# Lyra_Main_4_Panel.net
KiCad netlist of a schematic drawn in EAGLE
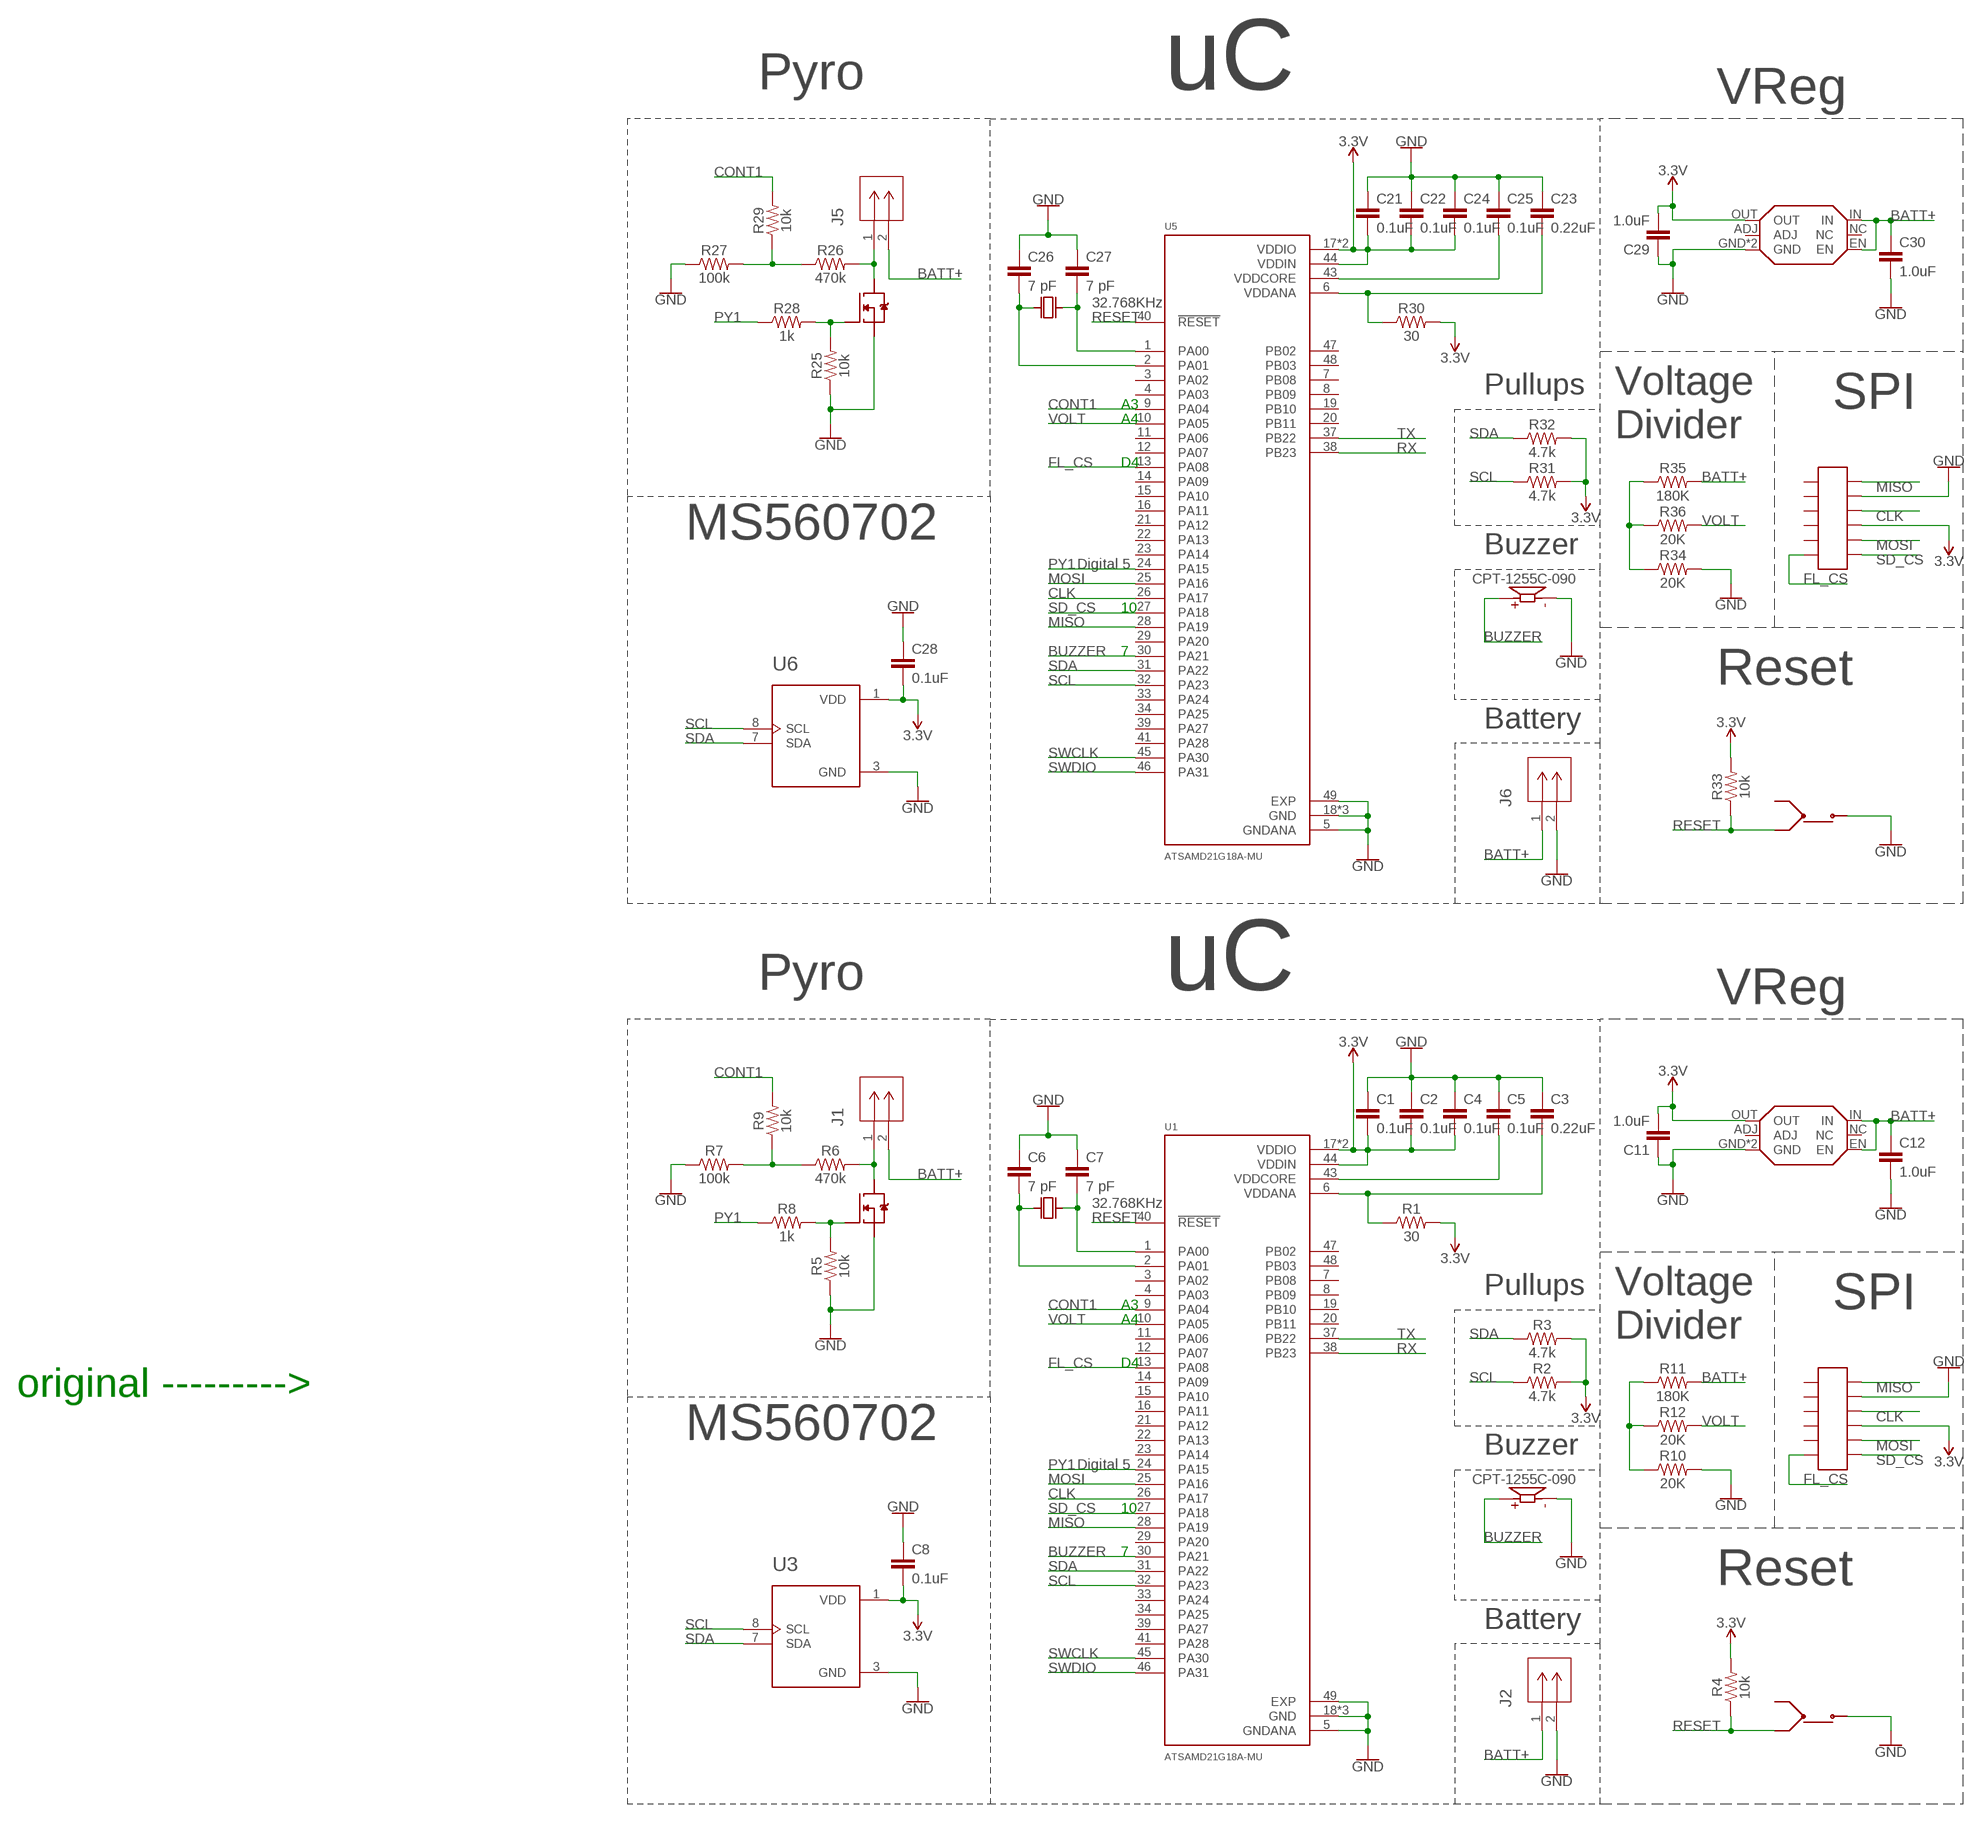
[diagram p0: schematic, sheet 1, part 1 of 2]
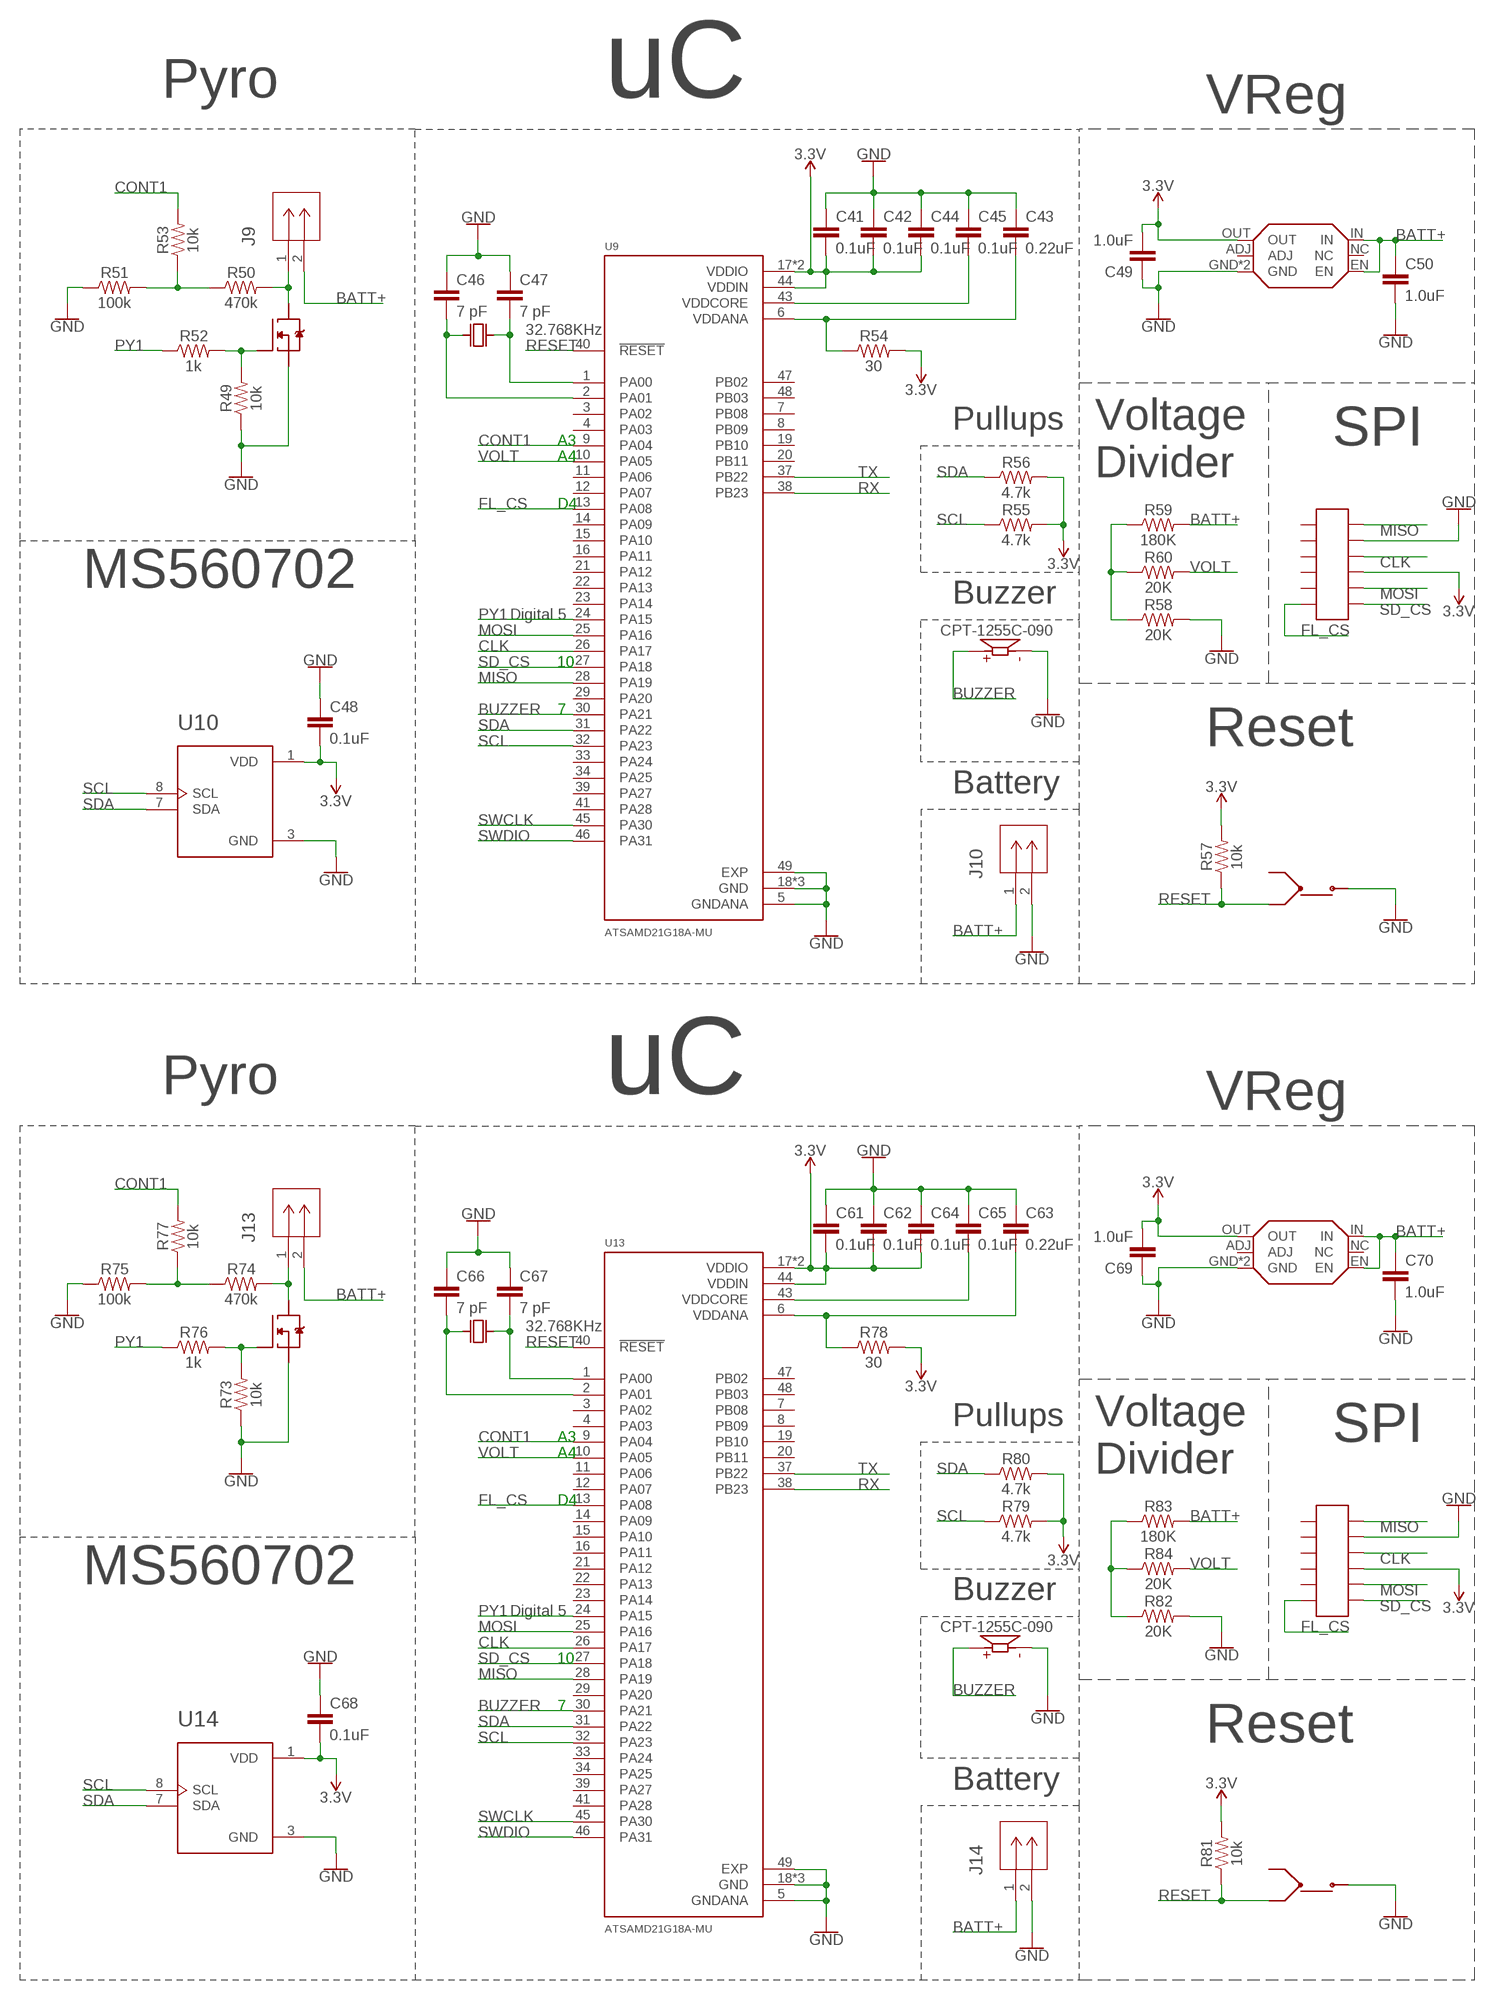
[diagram p1: schematic, sheet 1, part 2 of 2]

(export (version "E")
  (design (tool "Eeschema 10.0.6"))
  (components
    (comp (ref "C1")
      (value "0.1uF")
      (footprint "eagle-import:0603")
      (libsource (lib "eagle-import") (part "0.1UF-0603-25V-(+80/-20%)"))
    )
    (comp (ref "C2")
      (value "0.1uF")
      (footprint "eagle-import:0603")
      (libsource (lib "eagle-import") (part "0.1UF-0603-25V-(+80/-20%)"))
    )
    (comp (ref "C3")
      (value "0.22uF")
      (footprint "eagle-import:0603")
      (libsource (lib "eagle-import") (part "0.1UF-0603-25V-(+80/-20%)"))
    )
    (comp (ref "C4")
      (value "0.1uF")
      (footprint "eagle-import:0603")
      (libsource (lib "eagle-import") (part "0.1UF-0603-25V-(+80/-20%)"))
    )
    (comp (ref "C5")
      (value "0.1uF")
      (footprint "eagle-import:0603")
      (libsource (lib "eagle-import") (part "0.1UF-0603-25V-(+80/-20%)"))
    )
    (comp (ref "C6")
      (value "7 pF")
      (footprint "eagle-import:0402")
      (libsource (lib "eagle-import") (part "0.1UF-0402-16V-10%"))
    )
    (comp (ref "C7")
      (value "7 pF")
      (footprint "eagle-import:0402")
      (libsource (lib "eagle-import") (part "0.1UF-0402-16V-10%"))
    )
    (comp (ref "C8")
      (value "0.1uF")
      (footprint "eagle-import:0603")
      (libsource (lib "eagle-import") (part "0.1UF-0603-25V-(+80/-20%)"))
    )
    (comp (ref "C11")
      (value "1.0uF")
      (footprint "eagle-import:0402")
      (libsource (lib "eagle-import") (part "1.0UF-0402-16V-10%"))
    )
    (comp (ref "C12")
      (value "1.0uF")
      (footprint "eagle-import:0402")
      (libsource (lib "eagle-import") (part "1.0UF-0402-16V-10%"))
    )
    (comp (ref "C21")
      (value "0.1uF")
      (footprint "eagle-import:0603")
      (libsource (lib "eagle-import") (part "0.1UF-0603-25V-(+80/-20%)"))
    )
    (comp (ref "C22")
      (value "0.1uF")
      (footprint "eagle-import:0603")
      (libsource (lib "eagle-import") (part "0.1UF-0603-25V-(+80/-20%)"))
    )
    (comp (ref "C23")
      (value "0.22uF")
      (footprint "eagle-import:0603")
      (libsource (lib "eagle-import") (part "0.1UF-0603-25V-(+80/-20%)"))
    )
    (comp (ref "C24")
      (value "0.1uF")
      (footprint "eagle-import:0603")
      (libsource (lib "eagle-import") (part "0.1UF-0603-25V-(+80/-20%)"))
    )
    (comp (ref "C25")
      (value "0.1uF")
      (footprint "eagle-import:0603")
      (libsource (lib "eagle-import") (part "0.1UF-0603-25V-(+80/-20%)"))
    )
    (comp (ref "C26")
      (value "7 pF")
      (footprint "eagle-import:0402")
      (libsource (lib "eagle-import") (part "0.1UF-0402-16V-10%"))
    )
    (comp (ref "C27")
      (value "7 pF")
      (footprint "eagle-import:0402")
      (libsource (lib "eagle-import") (part "0.1UF-0402-16V-10%"))
    )
    (comp (ref "C28")
      (value "0.1uF")
      (footprint "eagle-import:0603")
      (libsource (lib "eagle-import") (part "0.1UF-0603-25V-(+80/-20%)"))
    )
    (comp (ref "C29")
      (value "1.0uF")
      (footprint "eagle-import:0402")
      (libsource (lib "eagle-import") (part "1.0UF-0402-16V-10%"))
    )
    (comp (ref "C30")
      (value "1.0uF")
      (footprint "eagle-import:0402")
      (libsource (lib "eagle-import") (part "1.0UF-0402-16V-10%"))
    )
    (comp (ref "C41")
      (value "0.1uF")
      (footprint "eagle-import:0603")
      (libsource (lib "eagle-import") (part "0.1UF-0603-25V-(+80/-20%)"))
    )
    (comp (ref "C42")
      (value "0.1uF")
      (footprint "eagle-import:0603")
      (libsource (lib "eagle-import") (part "0.1UF-0603-25V-(+80/-20%)"))
    )
    (comp (ref "C43")
      (value "0.22uF")
      (footprint "eagle-import:0603")
      (libsource (lib "eagle-import") (part "0.1UF-0603-25V-(+80/-20%)"))
    )
    (comp (ref "C44")
      (value "0.1uF")
      (footprint "eagle-import:0603")
      (libsource (lib "eagle-import") (part "0.1UF-0603-25V-(+80/-20%)"))
    )
    (comp (ref "C45")
      (value "0.1uF")
      (footprint "eagle-import:0603")
      (libsource (lib "eagle-import") (part "0.1UF-0603-25V-(+80/-20%)"))
    )
    (comp (ref "C46")
      (value "7 pF")
      (footprint "eagle-import:0402")
      (libsource (lib "eagle-import") (part "0.1UF-0402-16V-10%"))
    )
    (comp (ref "C47")
      (value "7 pF")
      (footprint "eagle-import:0402")
      (libsource (lib "eagle-import") (part "0.1UF-0402-16V-10%"))
    )
    (comp (ref "C48")
      (value "0.1uF")
      (footprint "eagle-import:0603")
      (libsource (lib "eagle-import") (part "0.1UF-0603-25V-(+80/-20%)"))
    )
    (comp (ref "C49")
      (value "1.0uF")
      (footprint "eagle-import:0402")
      (libsource (lib "eagle-import") (part "1.0UF-0402-16V-10%"))
    )
    (comp (ref "C50")
      (value "1.0uF")
      (footprint "eagle-import:0402")
      (libsource (lib "eagle-import") (part "1.0UF-0402-16V-10%"))
    )
    (comp (ref "C61")
      (value "0.1uF")
      (footprint "eagle-import:0603")
      (libsource (lib "eagle-import") (part "0.1UF-0603-25V-(+80/-20%)"))
    )
    (comp (ref "C62")
      (value "0.1uF")
      (footprint "eagle-import:0603")
      (libsource (lib "eagle-import") (part "0.1UF-0603-25V-(+80/-20%)"))
    )
    (comp (ref "C63")
      (value "0.22uF")
      (footprint "eagle-import:0603")
      (libsource (lib "eagle-import") (part "0.1UF-0603-25V-(+80/-20%)"))
    )
    (comp (ref "C64")
      (value "0.1uF")
      (footprint "eagle-import:0603")
      (libsource (lib "eagle-import") (part "0.1UF-0603-25V-(+80/-20%)"))
    )
    (comp (ref "C65")
      (value "0.1uF")
      (footprint "eagle-import:0603")
      (libsource (lib "eagle-import") (part "0.1UF-0603-25V-(+80/-20%)"))
    )
    (comp (ref "C66")
      (value "7 pF")
      (footprint "eagle-import:0402")
      (libsource (lib "eagle-import") (part "0.1UF-0402-16V-10%"))
    )
    (comp (ref "C67")
      (value "7 pF")
      (footprint "eagle-import:0402")
      (libsource (lib "eagle-import") (part "0.1UF-0402-16V-10%"))
    )
    (comp (ref "C68")
      (value "0.1uF")
      (footprint "eagle-import:0603")
      (libsource (lib "eagle-import") (part "0.1UF-0603-25V-(+80/-20%)"))
    )
    (comp (ref "C69")
      (value "1.0uF")
      (footprint "eagle-import:0402")
      (libsource (lib "eagle-import") (part "1.0UF-0402-16V-10%"))
    )
    (comp (ref "C70")
      (value "1.0uF")
      (footprint "eagle-import:0402")
      (libsource (lib "eagle-import") (part "1.0UF-0402-16V-10%"))
    )
    (comp (ref "J1")
      (value "OSTVN02A150")
      (footprint "eagle-import:CONN_OSTVN02A150_OST")
      (fields (field (name "COPYRIGHT") "Copyright (C) 2018 Accelerated Designs. All rights reserved"))
      (libsource (lib "eagle-import") (part "OSTVN02A150"))
    )
    (comp (ref "J2")
      (value "OSTVN02A150")
      (footprint "eagle-import:CONN_OSTVN02A150_OST")
      (fields (field (name "COPYRIGHT") "Copyright (C) 2018 Accelerated Designs. All rights reserved"))
      (libsource (lib "eagle-import") (part "OSTVN02A150"))
    )
    (comp (ref "J5")
      (value "OSTVN02A150")
      (footprint "eagle-import:CONN_OSTVN02A150_OST")
      (fields (field (name "COPYRIGHT") "Copyright (C) 2018 Accelerated Designs. All rights reserved"))
      (libsource (lib "eagle-import") (part "OSTVN02A150"))
    )
    (comp (ref "J6")
      (value "OSTVN02A150")
      (footprint "eagle-import:CONN_OSTVN02A150_OST")
      (fields (field (name "COPYRIGHT") "Copyright (C) 2018 Accelerated Designs. All rights reserved"))
      (libsource (lib "eagle-import") (part "OSTVN02A150"))
    )
    (comp (ref "J9")
      (value "OSTVN02A150")
      (footprint "eagle-import:CONN_OSTVN02A150_OST")
      (fields (field (name "COPYRIGHT") "Copyright (C) 2018 Accelerated Designs. All rights reserved"))
      (libsource (lib "eagle-import") (part "OSTVN02A150"))
    )
    (comp (ref "J10")
      (value "OSTVN02A150")
      (footprint "eagle-import:CONN_OSTVN02A150_OST")
      (fields (field (name "COPYRIGHT") "Copyright (C) 2018 Accelerated Designs. All rights reserved"))
      (libsource (lib "eagle-import") (part "OSTVN02A150"))
    )
    (comp (ref "J13")
      (value "OSTVN02A150")
      (footprint "eagle-import:CONN_OSTVN02A150_OST")
      (fields (field (name "COPYRIGHT") "Copyright (C) 2018 Accelerated Designs. All rights reserved"))
      (libsource (lib "eagle-import") (part "OSTVN02A150"))
    )
    (comp (ref "J14")
      (value "OSTVN02A150")
      (footprint "eagle-import:CONN_OSTVN02A150_OST")
      (fields (field (name "COPYRIGHT") "Copyright (C) 2018 Accelerated Designs. All rights reserved"))
      (libsource (lib "eagle-import") (part "OSTVN02A150"))
    )
    (comp (ref "LS2")
      (value "CPT-1255C-090")
      (footprint "eagle-import:CUI_CPT-1255C-090")
      (fields (field (name "MF") "CUI Devices"))
      (libsource (lib "eagle-import") (part "CPT-1255C-090"))
    )
    (comp (ref "LS3")
      (value "CPT-1255C-090")
      (footprint "eagle-import:CUI_CPT-1255C-090")
      (fields (field (name "MF") "CUI Devices"))
      (libsource (lib "eagle-import") (part "CPT-1255C-090"))
    )
    (comp (ref "LS5")
      (value "CPT-1255C-090")
      (footprint "eagle-import:CUI_CPT-1255C-090")
      (fields (field (name "MF") "CUI Devices"))
      (libsource (lib "eagle-import") (part "CPT-1255C-090"))
    )
    (comp (ref "LS7")
      (value "CPT-1255C-090")
      (footprint "eagle-import:CUI_CPT-1255C-090")
      (fields (field (name "MF") "CUI Devices"))
      (libsource (lib "eagle-import") (part "CPT-1255C-090"))
    )
    (comp (ref "R1")
      (value "30")
      (footprint "eagle-import:0402")
      (libsource (lib "eagle-import") (part "RESISTOR0402"))
    )
    (comp (ref "R2")
      (value "4.7k")
      (footprint "eagle-import:0603")
      (libsource (lib "eagle-import") (part "4.7KOHM-0603-1/10W-1%"))
    )
    (comp (ref "R3")
      (value "4.7k")
      (footprint "eagle-import:0603")
      (libsource (lib "eagle-import") (part "4.7KOHM-0603-1/10W-1%"))
    )
    (comp (ref "R4")
      (value "10k")
      (footprint "eagle-import:0402")
      (libsource (lib "eagle-import") (part "RESISTOR0402"))
    )
    (comp (ref "R5")
      (value "10k")
      (footprint "eagle-import:0402")
      (libsource (lib "eagle-import") (part "RESISTOR0402"))
    )
    (comp (ref "R6")
      (value "470k")
      (footprint "eagle-import:0402")
      (libsource (lib "eagle-import") (part "RESISTOR0402"))
    )
    (comp (ref "R7")
      (value "100k")
      (footprint "eagle-import:0402")
      (libsource (lib "eagle-import") (part "RESISTOR0402"))
    )
    (comp (ref "R8")
      (value "1k")
      (footprint "eagle-import:0402")
      (libsource (lib "eagle-import") (part "RESISTOR0402"))
    )
    (comp (ref "R9")
      (value "10k")
      (footprint "eagle-import:0402")
      (libsource (lib "eagle-import") (part "RESISTOR0402"))
    )
    (comp (ref "R10")
      (value "20K")
      (footprint "eagle-import:0402")
      (libsource (lib "eagle-import") (part "RESISTOR0402"))
    )
    (comp (ref "R11")
      (value "180K")
      (footprint "eagle-import:0402")
      (libsource (lib "eagle-import") (part "RESISTOR0402"))
    )
    (comp (ref "R12")
      (value "20K")
      (footprint "eagle-import:0402")
      (libsource (lib "eagle-import") (part "RESISTOR0402"))
    )
    (comp (ref "R25")
      (value "10k")
      (footprint "eagle-import:0402")
      (libsource (lib "eagle-import") (part "RESISTOR0402"))
    )
    (comp (ref "R26")
      (value "470k")
      (footprint "eagle-import:0402")
      (libsource (lib "eagle-import") (part "RESISTOR0402"))
    )
    (comp (ref "R27")
      (value "100k")
      (footprint "eagle-import:0402")
      (libsource (lib "eagle-import") (part "RESISTOR0402"))
    )
    (comp (ref "R28")
      (value "1k")
      (footprint "eagle-import:0402")
      (libsource (lib "eagle-import") (part "RESISTOR0402"))
    )
    (comp (ref "R29")
      (value "10k")
      (footprint "eagle-import:0402")
      (libsource (lib "eagle-import") (part "RESISTOR0402"))
    )
    (comp (ref "R30")
      (value "30")
      (footprint "eagle-import:0402")
      (libsource (lib "eagle-import") (part "RESISTOR0402"))
    )
    (comp (ref "R31")
      (value "4.7k")
      (footprint "eagle-import:0603")
      (libsource (lib "eagle-import") (part "4.7KOHM-0603-1/10W-1%"))
    )
    (comp (ref "R32")
      (value "4.7k")
      (footprint "eagle-import:0603")
      (libsource (lib "eagle-import") (part "4.7KOHM-0603-1/10W-1%"))
    )
    (comp (ref "R33")
      (value "10k")
      (footprint "eagle-import:0402")
      (libsource (lib "eagle-import") (part "RESISTOR0402"))
    )
    (comp (ref "R34")
      (value "20K")
      (footprint "eagle-import:0402")
      (libsource (lib "eagle-import") (part "RESISTOR0402"))
    )
    (comp (ref "R35")
      (value "180K")
      (footprint "eagle-import:0402")
      (libsource (lib "eagle-import") (part "RESISTOR0402"))
    )
    (comp (ref "R36")
      (value "20K")
      (footprint "eagle-import:0402")
      (libsource (lib "eagle-import") (part "RESISTOR0402"))
    )
    (comp (ref "R49")
      (value "10k")
      (footprint "eagle-import:0402")
      (libsource (lib "eagle-import") (part "RESISTOR0402"))
    )
    (comp (ref "R50")
      (value "470k")
      (footprint "eagle-import:0402")
      (libsource (lib "eagle-import") (part "RESISTOR0402"))
    )
    (comp (ref "R51")
      (value "100k")
      (footprint "eagle-import:0402")
      (libsource (lib "eagle-import") (part "RESISTOR0402"))
    )
    (comp (ref "R52")
      (value "1k")
      (footprint "eagle-import:0402")
      (libsource (lib "eagle-import") (part "RESISTOR0402"))
    )
    (comp (ref "R53")
      (value "10k")
      (footprint "eagle-import:0402")
      (libsource (lib "eagle-import") (part "RESISTOR0402"))
    )
    (comp (ref "R54")
      (value "30")
      (footprint "eagle-import:0402")
      (libsource (lib "eagle-import") (part "RESISTOR0402"))
    )
    (comp (ref "R55")
      (value "4.7k")
      (footprint "eagle-import:0603")
      (libsource (lib "eagle-import") (part "4.7KOHM-0603-1/10W-1%"))
    )
    (comp (ref "R56")
      (value "4.7k")
      (footprint "eagle-import:0603")
      (libsource (lib "eagle-import") (part "4.7KOHM-0603-1/10W-1%"))
    )
    (comp (ref "R57")
      (value "10k")
      (footprint "eagle-import:0402")
      (libsource (lib "eagle-import") (part "RESISTOR0402"))
    )
    (comp (ref "R58")
      (value "20K")
      (footprint "eagle-import:0402")
      (libsource (lib "eagle-import") (part "RESISTOR0402"))
    )
    (comp (ref "R59")
      (value "180K")
      (footprint "eagle-import:0402")
      (libsource (lib "eagle-import") (part "RESISTOR0402"))
    )
    (comp (ref "R60")
      (value "20K")
      (footprint "eagle-import:0402")
      (libsource (lib "eagle-import") (part "RESISTOR0402"))
    )
    (comp (ref "R73")
      (value "10k")
      (footprint "eagle-import:0402")
      (libsource (lib "eagle-import") (part "RESISTOR0402"))
    )
    (comp (ref "R74")
      (value "470k")
      (footprint "eagle-import:0402")
      (libsource (lib "eagle-import") (part "RESISTOR0402"))
    )
    (comp (ref "R75")
      (value "100k")
      (footprint "eagle-import:0402")
      (libsource (lib "eagle-import") (part "RESISTOR0402"))
    )
    (comp (ref "R76")
      (value "1k")
      (footprint "eagle-import:0402")
      (libsource (lib "eagle-import") (part "RESISTOR0402"))
    )
    (comp (ref "R77")
      (value "10k")
      (footprint "eagle-import:0402")
      (libsource (lib "eagle-import") (part "RESISTOR0402"))
    )
    (comp (ref "R78")
      (value "30")
      (footprint "eagle-import:0402")
      (libsource (lib "eagle-import") (part "RESISTOR0402"))
    )
    (comp (ref "R79")
      (value "4.7k")
      (footprint "eagle-import:0603")
      (libsource (lib "eagle-import") (part "4.7KOHM-0603-1/10W-1%"))
    )
    (comp (ref "R80")
      (value "4.7k")
      (footprint "eagle-import:0603")
      (libsource (lib "eagle-import") (part "4.7KOHM-0603-1/10W-1%"))
    )
    (comp (ref "R81")
      (value "10k")
      (footprint "eagle-import:0402")
      (libsource (lib "eagle-import") (part "RESISTOR0402"))
    )
    (comp (ref "R82")
      (value "20K")
      (footprint "eagle-import:0402")
      (libsource (lib "eagle-import") (part "RESISTOR0402"))
    )
    (comp (ref "R83")
      (value "180K")
      (footprint "eagle-import:0402")
      (libsource (lib "eagle-import") (part "RESISTOR0402"))
    )
    (comp (ref "R84")
      (value "20K")
      (footprint "eagle-import:0402")
      (libsource (lib "eagle-import") (part "RESISTOR0402"))
    )
    (comp (ref "U$1")
      (value "32.768KHz")
      (footprint "eagle-import:FC-135")
      (libsource (lib "eagle-import") (part "FC-135"))
    )
    (comp (ref "U$2")
      (value "IRLHM630PBF")
      (footprint "eagle-import:IRLHM630PBF")
      (libsource (lib "eagle-import") (part "IRLHM630PBF"))
    )
    (comp (ref "U$3")
      (value "NCP718AMT330TBG")
      (footprint "eagle-import:NCP718BMT330TBG")
      (libsource (lib "eagle-import") (part "NCP718AMT330TBG"))
    )
    (comp (ref "U$4")
      (value "BUTTON")
      (footprint "eagle-import:BUTTON")
      (libsource (lib "eagle-import") (part "BUTTON"))
    )
    (comp (ref "U$5")
      (value "12POS_SOCKET")
      (footprint "eagle-import:12POS_SOCKET")
      (libsource (lib "eagle-import") (part "12POS_SOCKET"))
    )
    (comp (ref "U$11")
      (value "IRLHM630PBF")
      (footprint "eagle-import:IRLHM630PBF")
      (libsource (lib "eagle-import") (part "IRLHM630PBF"))
    )
    (comp (ref "U$12")
      (value "32.768KHz")
      (footprint "eagle-import:FC-135")
      (libsource (lib "eagle-import") (part "FC-135"))
    )
    (comp (ref "U$13")
      (value "NCP718AMT330TBG")
      (footprint "eagle-import:NCP718BMT330TBG")
      (libsource (lib "eagle-import") (part "NCP718AMT330TBG"))
    )
    (comp (ref "U$14")
      (value "BUTTON")
      (footprint "eagle-import:BUTTON")
      (libsource (lib "eagle-import") (part "BUTTON"))
    )
    (comp (ref "U$15")
      (value "12POS_SOCKET")
      (footprint "eagle-import:12POS_SOCKET")
      (libsource (lib "eagle-import") (part "12POS_SOCKET"))
    )
    (comp (ref "U$21")
      (value "IRLHM630PBF")
      (footprint "eagle-import:IRLHM630PBF")
      (libsource (lib "eagle-import") (part "IRLHM630PBF"))
    )
    (comp (ref "U$22")
      (value "32.768KHz")
      (footprint "eagle-import:FC-135")
      (libsource (lib "eagle-import") (part "FC-135"))
    )
    (comp (ref "U$23")
      (value "NCP718AMT330TBG")
      (footprint "eagle-import:NCP718BMT330TBG")
      (libsource (lib "eagle-import") (part "NCP718AMT330TBG"))
    )
    (comp (ref "U$24")
      (value "BUTTON")
      (footprint "eagle-import:BUTTON")
      (libsource (lib "eagle-import") (part "BUTTON"))
    )
    (comp (ref "U$25")
      (value "12POS_SOCKET")
      (footprint "eagle-import:12POS_SOCKET")
      (libsource (lib "eagle-import") (part "12POS_SOCKET"))
    )
    (comp (ref "U$31")
      (value "IRLHM630PBF")
      (footprint "eagle-import:IRLHM630PBF")
      (libsource (lib "eagle-import") (part "IRLHM630PBF"))
    )
    (comp (ref "U$32")
      (value "32.768KHz")
      (footprint "eagle-import:FC-135")
      (libsource (lib "eagle-import") (part "FC-135"))
    )
    (comp (ref "U$33")
      (value "NCP718AMT330TBG")
      (footprint "eagle-import:NCP718BMT330TBG")
      (libsource (lib "eagle-import") (part "NCP718AMT330TBG"))
    )
    (comp (ref "U$34")
      (value "BUTTON")
      (footprint "eagle-import:BUTTON")
      (libsource (lib "eagle-import") (part "BUTTON"))
    )
    (comp (ref "U$35")
      (value "12POS_SOCKET")
      (footprint "eagle-import:12POS_SOCKET")
      (libsource (lib "eagle-import") (part "12POS_SOCKET"))
    )
    (comp (ref "U1")
      (value "ATSAMD21G18A-MU")
      (footprint "eagle-import:QFN50P700X700X90-49N")
      (fields (field (name "DIGI-KEY_PART_NUMBER") "ATSAMD21G18A-MUTTR-ND") (field (name "MF") "Microchip"))
      (libsource (lib "eagle-import") (part "ATSAMD21G18A-MU"))
    )
    (comp (ref "U3")
      (value "MS860702BA01-50")
      (footprint "eagle-import:TE_MS860702BA01-50")
      (fields (field (name "MF") "TE Connectivity"))
      (libsource (lib "eagle-import") (part "MS860702BA01-50"))
    )
    (comp (ref "U5")
      (value "ATSAMD21G18A-MU")
      (footprint "eagle-import:QFN50P700X700X90-49N")
      (fields (field (name "DIGI-KEY_PART_NUMBER") "ATSAMD21G18A-MUTTR-ND") (field (name "MF") "Microchip"))
      (libsource (lib "eagle-import") (part "ATSAMD21G18A-MU"))
    )
    (comp (ref "U6")
      (value "MS860702BA01-50")
      (footprint "eagle-import:TE_MS860702BA01-50")
      (fields (field (name "MF") "TE Connectivity"))
      (libsource (lib "eagle-import") (part "MS860702BA01-50"))
    )
    (comp (ref "U9")
      (value "ATSAMD21G18A-MU")
      (footprint "eagle-import:QFN50P700X700X90-49N")
      (fields (field (name "DIGI-KEY_PART_NUMBER") "ATSAMD21G18A-MUTTR-ND") (field (name "MF") "Microchip"))
      (libsource (lib "eagle-import") (part "ATSAMD21G18A-MU"))
    )
    (comp (ref "U10")
      (value "MS860702BA01-50")
      (footprint "eagle-import:TE_MS860702BA01-50")
      (fields (field (name "MF") "TE Connectivity"))
      (libsource (lib "eagle-import") (part "MS860702BA01-50"))
    )
    (comp (ref "U13")
      (value "ATSAMD21G18A-MU")
      (footprint "eagle-import:QFN50P700X700X90-49N")
      (fields (field (name "DIGI-KEY_PART_NUMBER") "ATSAMD21G18A-MUTTR-ND") (field (name "MF") "Microchip"))
      (libsource (lib "eagle-import") (part "ATSAMD21G18A-MU"))
    )
    (comp (ref "U14")
      (value "MS860702BA01-50")
      (footprint "eagle-import:TE_MS860702BA01-50")
      (fields (field (name "MF") "TE Connectivity"))
      (libsource (lib "eagle-import") (part "MS860702BA01-50"))
    )
  )
  (nets
    (net (code "1") (name "/BATT+") (class "Default")
      (node (ref "C12") (pin "1") (pinfunction "1_1") (pintype "passive"))
      (node (ref "C30") (pin "1") (pinfunction "1_1") (pintype "passive"))
      (node (ref "C50") (pin "1") (pinfunction "1_1") (pintype "passive"))
      (node (ref "C70") (pin "1") (pinfunction "1_1") (pintype "passive"))
      (node (ref "J1") (pin "2") (pinfunction "2_2") (pintype "passive"))
      (node (ref "J10") (pin "1") (pinfunction "1_1") (pintype "passive"))
      (node (ref "J13") (pin "2") (pinfunction "2_2") (pintype "passive"))
      (node (ref "J14") (pin "1") (pinfunction "1_1") (pintype "passive"))
      (node (ref "J2") (pin "1") (pinfunction "1_1") (pintype "passive"))
      (node (ref "J5") (pin "2") (pinfunction "2_2") (pintype "passive"))
      (node (ref "J6") (pin "1") (pinfunction "1_1") (pintype "passive"))
      (node (ref "J9") (pin "2") (pinfunction "2_2") (pintype "passive"))
      (node (ref "R11") (pin "2") (pinfunction "2_2") (pintype "passive"))
      (node (ref "R35") (pin "2") (pinfunction "2_2") (pintype "passive"))
      (node (ref "R59") (pin "2") (pinfunction "2_2") (pintype "passive"))
      (node (ref "R83") (pin "2") (pinfunction "2_2") (pintype "passive"))
      (node (ref "U$13") (pin "EN") (pinfunction "EN_EN") (pintype "bidirectional"))
      (node (ref "U$13") (pin "IN") (pinfunction "IN_IN") (pintype "bidirectional"))
      (node (ref "U$23") (pin "EN") (pinfunction "EN_EN") (pintype "bidirectional"))
      (node (ref "U$23") (pin "IN") (pinfunction "IN_IN") (pintype "bidirectional"))
      (node (ref "U$3") (pin "EN") (pinfunction "EN_EN") (pintype "bidirectional"))
      (node (ref "U$3") (pin "IN") (pinfunction "IN_IN") (pintype "bidirectional"))
      (node (ref "U$33") (pin "EN") (pinfunction "EN_EN") (pintype "bidirectional"))
      (node (ref "U$33") (pin "IN") (pinfunction "IN_IN") (pintype "bidirectional"))
    )
    (net (code "2") (name "/BUZZER") (class "Default")
      (node (ref "LS2") (pin "P") (pinfunction "P_P") (pintype "passive"))
      (node (ref "LS3") (pin "P") (pinfunction "P_P") (pintype "passive"))
      (node (ref "LS5") (pin "P") (pinfunction "P_P") (pintype "passive"))
      (node (ref "LS7") (pin "P") (pinfunction "P_P") (pintype "passive"))
      (node (ref "U1") (pin "30") (pinfunction "PA21_30") (pintype "bidirectional"))
      (node (ref "U13") (pin "30") (pinfunction "PA21_30") (pintype "bidirectional"))
      (node (ref "U5") (pin "30") (pinfunction "PA21_30") (pintype "bidirectional"))
      (node (ref "U9") (pin "30") (pinfunction "PA21_30") (pintype "bidirectional"))
    )
    (net (code "3") (name "/CLK") (class "Default")
      (node (ref "U$15") (pin "P$10") (pinfunction "P$10_P$10") (pintype "bidirectional"))
      (node (ref "U$25") (pin "P$10") (pinfunction "P$10_P$10") (pintype "bidirectional"))
      (node (ref "U$35") (pin "P$10") (pinfunction "P$10_P$10") (pintype "bidirectional"))
      (node (ref "U$5") (pin "P$10") (pinfunction "P$10_P$10") (pintype "bidirectional"))
      (node (ref "U1") (pin "26") (pinfunction "PA17_26") (pintype "bidirectional"))
      (node (ref "U13") (pin "26") (pinfunction "PA17_26") (pintype "bidirectional"))
      (node (ref "U5") (pin "26") (pinfunction "PA17_26") (pintype "bidirectional"))
      (node (ref "U9") (pin "26") (pinfunction "PA17_26") (pintype "bidirectional"))
    )
    (net (code "4") (name "/CONT1") (class "Default")
      (node (ref "R29") (pin "2") (pinfunction "2_2") (pintype "passive"))
      (node (ref "R53") (pin "2") (pinfunction "2_2") (pintype "passive"))
      (node (ref "R77") (pin "2") (pinfunction "2_2") (pintype "passive"))
      (node (ref "R9") (pin "2") (pinfunction "2_2") (pintype "passive"))
      (node (ref "U1") (pin "9") (pinfunction "PA04_9") (pintype "bidirectional"))
      (node (ref "U13") (pin "9") (pinfunction "PA04_9") (pintype "bidirectional"))
      (node (ref "U5") (pin "9") (pinfunction "PA04_9") (pintype "bidirectional"))
      (node (ref "U9") (pin "9") (pinfunction "PA04_9") (pintype "bidirectional"))
    )
    (net (code "5") (name "/FL_CS") (class "Default")
      (node (ref "U$15") (pin "P$6") (pinfunction "P$6_P$6") (pintype "bidirectional"))
      (node (ref "U$25") (pin "P$6") (pinfunction "P$6_P$6") (pintype "bidirectional"))
      (node (ref "U$35") (pin "P$6") (pinfunction "P$6_P$6") (pintype "bidirectional"))
      (node (ref "U$5") (pin "P$6") (pinfunction "P$6_P$6") (pintype "bidirectional"))
      (node (ref "U1") (pin "13") (pinfunction "PA08_13") (pintype "bidirectional"))
      (node (ref "U13") (pin "13") (pinfunction "PA08_13") (pintype "bidirectional"))
      (node (ref "U5") (pin "13") (pinfunction "PA08_13") (pintype "bidirectional"))
      (node (ref "U9") (pin "13") (pinfunction "PA08_13") (pintype "bidirectional"))
    )
    (net (code "6") (name "/MISO") (class "Default")
      (node (ref "U$15") (pin "P$12") (pinfunction "P$12_P$12") (pintype "bidirectional"))
      (node (ref "U$25") (pin "P$12") (pinfunction "P$12_P$12") (pintype "bidirectional"))
      (node (ref "U$35") (pin "P$12") (pinfunction "P$12_P$12") (pintype "bidirectional"))
      (node (ref "U$5") (pin "P$12") (pinfunction "P$12_P$12") (pintype "bidirectional"))
      (node (ref "U1") (pin "28") (pinfunction "PA19_28") (pintype "bidirectional"))
      (node (ref "U13") (pin "28") (pinfunction "PA19_28") (pintype "bidirectional"))
      (node (ref "U5") (pin "28") (pinfunction "PA19_28") (pintype "bidirectional"))
      (node (ref "U9") (pin "28") (pinfunction "PA19_28") (pintype "bidirectional"))
    )
    (net (code "7") (name "/MOSI") (class "Default")
      (node (ref "U$15") (pin "P$8") (pinfunction "P$8_P$8") (pintype "bidirectional"))
      (node (ref "U$25") (pin "P$8") (pinfunction "P$8_P$8") (pintype "bidirectional"))
      (node (ref "U$35") (pin "P$8") (pinfunction "P$8_P$8") (pintype "bidirectional"))
      (node (ref "U$5") (pin "P$8") (pinfunction "P$8_P$8") (pintype "bidirectional"))
      (node (ref "U1") (pin "25") (pinfunction "PA16_25") (pintype "bidirectional"))
      (node (ref "U13") (pin "25") (pinfunction "PA16_25") (pintype "bidirectional"))
      (node (ref "U5") (pin "25") (pinfunction "PA16_25") (pintype "bidirectional"))
      (node (ref "U9") (pin "25") (pinfunction "PA16_25") (pintype "bidirectional"))
    )
    (net (code "8") (name "/PY1") (class "Default")
      (node (ref "R28") (pin "1") (pinfunction "1_1") (pintype "passive"))
      (node (ref "R52") (pin "1") (pinfunction "1_1") (pintype "passive"))
      (node (ref "R76") (pin "1") (pinfunction "1_1") (pintype "passive"))
      (node (ref "R8") (pin "1") (pinfunction "1_1") (pintype "passive"))
      (node (ref "U1") (pin "24") (pinfunction "PA15_24") (pintype "bidirectional"))
      (node (ref "U13") (pin "24") (pinfunction "PA15_24") (pintype "bidirectional"))
      (node (ref "U5") (pin "24") (pinfunction "PA15_24") (pintype "bidirectional"))
      (node (ref "U9") (pin "24") (pinfunction "PA15_24") (pintype "bidirectional"))
    )
    (net (code "9") (name "/RESET") (class "Default")
      (node (ref "R33") (pin "1") (pinfunction "1_1") (pintype "passive"))
      (node (ref "R4") (pin "1") (pinfunction "1_1") (pintype "passive"))
      (node (ref "R57") (pin "1") (pinfunction "1_1") (pintype "passive"))
      (node (ref "R81") (pin "1") (pinfunction "1_1") (pintype "passive"))
      (node (ref "U$14") (pin "2") (pinfunction "IN(2)_2") (pintype "bidirectional"))
      (node (ref "U$24") (pin "2") (pinfunction "IN(2)_2") (pintype "bidirectional"))
      (node (ref "U$34") (pin "2") (pinfunction "IN(2)_2") (pintype "bidirectional"))
      (node (ref "U$4") (pin "2") (pinfunction "IN(2)_2") (pintype "bidirectional"))
      (node (ref "U1") (pin "40") (pinfunction "~{RESET}_40") (pintype "input"))
      (node (ref "U13") (pin "40") (pinfunction "~{RESET}_40") (pintype "input"))
      (node (ref "U5") (pin "40") (pinfunction "~{RESET}_40") (pintype "input"))
      (node (ref "U9") (pin "40") (pinfunction "~{RESET}_40") (pintype "input"))
    )
    (net (code "10") (name "/RX") (class "Default")
      (node (ref "U1") (pin "38") (pinfunction "PB23_38") (pintype "bidirectional"))
      (node (ref "U13") (pin "38") (pinfunction "PB23_38") (pintype "bidirectional"))
      (node (ref "U5") (pin "38") (pinfunction "PB23_38") (pintype "bidirectional"))
      (node (ref "U9") (pin "38") (pinfunction "PB23_38") (pintype "bidirectional"))
    )
    (net (code "11") (name "/SCL") (class "Default")
      (node (ref "R2") (pin "1") (pinfunction "1_1") (pintype "passive"))
      (node (ref "R31") (pin "1") (pinfunction "1_1") (pintype "passive"))
      (node (ref "R55") (pin "1") (pinfunction "1_1") (pintype "passive"))
      (node (ref "R79") (pin "1") (pinfunction "1_1") (pintype "passive"))
      (node (ref "U1") (pin "32") (pinfunction "PA23_32") (pintype "bidirectional"))
      (node (ref "U10") (pin "8") (pinfunction "SCL_8") (pintype "input"))
      (node (ref "U13") (pin "32") (pinfunction "PA23_32") (pintype "bidirectional"))
      (node (ref "U14") (pin "8") (pinfunction "SCL_8") (pintype "input"))
      (node (ref "U3") (pin "8") (pinfunction "SCL_8") (pintype "input"))
      (node (ref "U5") (pin "32") (pinfunction "PA23_32") (pintype "bidirectional"))
      (node (ref "U6") (pin "8") (pinfunction "SCL_8") (pintype "input"))
      (node (ref "U9") (pin "32") (pinfunction "PA23_32") (pintype "bidirectional"))
    )
    (net (code "12") (name "/SDA") (class "Default")
      (node (ref "R3") (pin "1") (pinfunction "1_1") (pintype "passive"))
      (node (ref "R32") (pin "1") (pinfunction "1_1") (pintype "passive"))
      (node (ref "R56") (pin "1") (pinfunction "1_1") (pintype "passive"))
      (node (ref "R80") (pin "1") (pinfunction "1_1") (pintype "passive"))
      (node (ref "U1") (pin "31") (pinfunction "PA22_31") (pintype "bidirectional"))
      (node (ref "U10") (pin "7") (pinfunction "SDA_7") (pintype "bidirectional"))
      (node (ref "U13") (pin "31") (pinfunction "PA22_31") (pintype "bidirectional"))
      (node (ref "U14") (pin "7") (pinfunction "SDA_7") (pintype "bidirectional"))
      (node (ref "U3") (pin "7") (pinfunction "SDA_7") (pintype "bidirectional"))
      (node (ref "U5") (pin "31") (pinfunction "PA22_31") (pintype "bidirectional"))
      (node (ref "U6") (pin "7") (pinfunction "SDA_7") (pintype "bidirectional"))
      (node (ref "U9") (pin "31") (pinfunction "PA22_31") (pintype "bidirectional"))
    )
    (net (code "13") (name "/SD_CS") (class "Default")
      (node (ref "U$15") (pin "P$7") (pinfunction "P$7_P$7") (pintype "bidirectional"))
      (node (ref "U$25") (pin "P$7") (pinfunction "P$7_P$7") (pintype "bidirectional"))
      (node (ref "U$35") (pin "P$7") (pinfunction "P$7_P$7") (pintype "bidirectional"))
      (node (ref "U$5") (pin "P$7") (pinfunction "P$7_P$7") (pintype "bidirectional"))
      (node (ref "U1") (pin "27") (pinfunction "PA18_27") (pintype "bidirectional"))
      (node (ref "U13") (pin "27") (pinfunction "PA18_27") (pintype "bidirectional"))
      (node (ref "U5") (pin "27") (pinfunction "PA18_27") (pintype "bidirectional"))
      (node (ref "U9") (pin "27") (pinfunction "PA18_27") (pintype "bidirectional"))
    )
    (net (code "14") (name "/SWCLK") (class "Default")
      (node (ref "U1") (pin "45") (pinfunction "PA30_45") (pintype "bidirectional"))
      (node (ref "U13") (pin "45") (pinfunction "PA30_45") (pintype "bidirectional"))
      (node (ref "U5") (pin "45") (pinfunction "PA30_45") (pintype "bidirectional"))
      (node (ref "U9") (pin "45") (pinfunction "PA30_45") (pintype "bidirectional"))
    )
    (net (code "15") (name "/SWDIO") (class "Default")
      (node (ref "U1") (pin "46") (pinfunction "PA31_46") (pintype "bidirectional"))
      (node (ref "U13") (pin "46") (pinfunction "PA31_46") (pintype "bidirectional"))
      (node (ref "U5") (pin "46") (pinfunction "PA31_46") (pintype "bidirectional"))
      (node (ref "U9") (pin "46") (pinfunction "PA31_46") (pintype "bidirectional"))
    )
    (net (code "16") (name "/TX") (class "Default")
      (node (ref "U1") (pin "37") (pinfunction "PB22_37") (pintype "bidirectional"))
      (node (ref "U13") (pin "37") (pinfunction "PB22_37") (pintype "bidirectional"))
      (node (ref "U5") (pin "37") (pinfunction "PB22_37") (pintype "bidirectional"))
      (node (ref "U9") (pin "37") (pinfunction "PB22_37") (pintype "bidirectional"))
    )
    (net (code "17") (name "/VOLT") (class "Default")
      (node (ref "R12") (pin "2") (pinfunction "2_2") (pintype "passive"))
      (node (ref "R36") (pin "2") (pinfunction "2_2") (pintype "passive"))
      (node (ref "R60") (pin "2") (pinfunction "2_2") (pintype "passive"))
      (node (ref "R84") (pin "2") (pinfunction "2_2") (pintype "passive"))
      (node (ref "U1") (pin "10") (pinfunction "PA05_10") (pintype "bidirectional"))
      (node (ref "U13") (pin "10") (pinfunction "PA05_10") (pintype "bidirectional"))
      (node (ref "U5") (pin "10") (pinfunction "PA05_10") (pintype "bidirectional"))
      (node (ref "U9") (pin "10") (pinfunction "PA05_10") (pintype "bidirectional"))
    )
    (net (code "18") (name "3.3V") (class "Default")
      (node (ref "C1") (pin "2") (pinfunction "2_2") (pintype "passive"))
      (node (ref "C11") (pin "2") (pinfunction "2_2") (pintype "passive"))
      (node (ref "C2") (pin "2") (pinfunction "2_2") (pintype "passive"))
      (node (ref "C21") (pin "2") (pinfunction "2_2") (pintype "passive"))
      (node (ref "C22") (pin "2") (pinfunction "2_2") (pintype "passive"))
      (node (ref "C24") (pin "2") (pinfunction "2_2") (pintype "passive"))
      (node (ref "C28") (pin "2") (pinfunction "2_2") (pintype "passive"))
      (node (ref "C29") (pin "2") (pinfunction "2_2") (pintype "passive"))
      (node (ref "C4") (pin "2") (pinfunction "2_2") (pintype "passive"))
      (node (ref "C41") (pin "2") (pinfunction "2_2") (pintype "passive"))
      (node (ref "C42") (pin "2") (pinfunction "2_2") (pintype "passive"))
      (node (ref "C44") (pin "2") (pinfunction "2_2") (pintype "passive"))
      (node (ref "C48") (pin "2") (pinfunction "2_2") (pintype "passive"))
      (node (ref "C49") (pin "2") (pinfunction "2_2") (pintype "passive"))
      (node (ref "C61") (pin "2") (pinfunction "2_2") (pintype "passive"))
      (node (ref "C62") (pin "2") (pinfunction "2_2") (pintype "passive"))
      (node (ref "C64") (pin "2") (pinfunction "2_2") (pintype "passive"))
      (node (ref "C68") (pin "2") (pinfunction "2_2") (pintype "passive"))
      (node (ref "C69") (pin "2") (pinfunction "2_2") (pintype "passive"))
      (node (ref "C8") (pin "2") (pinfunction "2_2") (pintype "passive"))
      (node (ref "R1") (pin "2") (pinfunction "2_2") (pintype "passive"))
      (node (ref "R2") (pin "2") (pinfunction "2_2") (pintype "passive"))
      (node (ref "R3") (pin "2") (pinfunction "2_2") (pintype "passive"))
      (node (ref "R30") (pin "2") (pinfunction "2_2") (pintype "passive"))
      (node (ref "R31") (pin "2") (pinfunction "2_2") (pintype "passive"))
      (node (ref "R32") (pin "2") (pinfunction "2_2") (pintype "passive"))
      (node (ref "R33") (pin "2") (pinfunction "2_2") (pintype "passive"))
      (node (ref "R4") (pin "2") (pinfunction "2_2") (pintype "passive"))
      (node (ref "R54") (pin "2") (pinfunction "2_2") (pintype "passive"))
      (node (ref "R55") (pin "2") (pinfunction "2_2") (pintype "passive"))
      (node (ref "R56") (pin "2") (pinfunction "2_2") (pintype "passive"))
      (node (ref "R57") (pin "2") (pinfunction "2_2") (pintype "passive"))
      (node (ref "R78") (pin "2") (pinfunction "2_2") (pintype "passive"))
      (node (ref "R79") (pin "2") (pinfunction "2_2") (pintype "passive"))
      (node (ref "R80") (pin "2") (pinfunction "2_2") (pintype "passive"))
      (node (ref "R81") (pin "2") (pinfunction "2_2") (pintype "passive"))
      (node (ref "U$13") (pin "OUT") (pinfunction "OUT_OUT") (pintype "bidirectional"))
      (node (ref "U$15") (pin "P$9") (pinfunction "P$9_P$9") (pintype "bidirectional"))
      (node (ref "U$23") (pin "OUT") (pinfunction "OUT_OUT") (pintype "bidirectional"))
      (node (ref "U$25") (pin "P$9") (pinfunction "P$9_P$9") (pintype "bidirectional"))
      (node (ref "U$3") (pin "OUT") (pinfunction "OUT_OUT") (pintype "bidirectional"))
      (node (ref "U$33") (pin "OUT") (pinfunction "OUT_OUT") (pintype "bidirectional"))
      (node (ref "U$35") (pin "P$9") (pinfunction "P$9_P$9") (pintype "bidirectional"))
      (node (ref "U$5") (pin "P$9") (pinfunction "P$9_P$9") (pintype "bidirectional"))
      (node (ref "U1") (pin "17") (pinfunction "VDDIO_17") (pintype "power_in"))
      (node (ref "U1") (pin "36") (pinfunction "VDDIO_36") (pintype "power_in"))
      (node (ref "U1") (pin "44") (pinfunction "VDDIN_44") (pintype "power_in"))
      (node (ref "U10") (pin "1") (pinfunction "VDD_1") (pintype "power_in"))
      (node (ref "U13") (pin "17") (pinfunction "VDDIO_17") (pintype "power_in"))
      (node (ref "U13") (pin "36") (pinfunction "VDDIO_36") (pintype "power_in"))
      (node (ref "U13") (pin "44") (pinfunction "VDDIN_44") (pintype "power_in"))
      (node (ref "U14") (pin "1") (pinfunction "VDD_1") (pintype "power_in"))
      (node (ref "U3") (pin "1") (pinfunction "VDD_1") (pintype "power_in"))
      (node (ref "U5") (pin "17") (pinfunction "VDDIO_17") (pintype "power_in"))
      (node (ref "U5") (pin "36") (pinfunction "VDDIO_36") (pintype "power_in"))
      (node (ref "U5") (pin "44") (pinfunction "VDDIN_44") (pintype "power_in"))
      (node (ref "U6") (pin "1") (pinfunction "VDD_1") (pintype "power_in"))
      (node (ref "U9") (pin "17") (pinfunction "VDDIO_17") (pintype "power_in"))
      (node (ref "U9") (pin "36") (pinfunction "VDDIO_36") (pintype "power_in"))
      (node (ref "U9") (pin "44") (pinfunction "VDDIN_44") (pintype "power_in"))
    )
    (net (code "19") (name "GND") (class "Default")
      (node (ref "C1") (pin "1") (pinfunction "1_1") (pintype "passive"))
      (node (ref "C11") (pin "1") (pinfunction "1_1") (pintype "passive"))
      (node (ref "C12") (pin "2") (pinfunction "2_2") (pintype "passive"))
      (node (ref "C2") (pin "1") (pinfunction "1_1") (pintype "passive"))
      (node (ref "C21") (pin "1") (pinfunction "1_1") (pintype "passive"))
      (node (ref "C22") (pin "1") (pinfunction "1_1") (pintype "passive"))
      (node (ref "C23") (pin "1") (pinfunction "1_1") (pintype "passive"))
      (node (ref "C24") (pin "1") (pinfunction "1_1") (pintype "passive"))
      (node (ref "C25") (pin "1") (pinfunction "1_1") (pintype "passive"))
      (node (ref "C26") (pin "1") (pinfunction "1_1") (pintype "passive"))
      (node (ref "C27") (pin "1") (pinfunction "1_1") (pintype "passive"))
      (node (ref "C28") (pin "1") (pinfunction "1_1") (pintype "passive"))
      (node (ref "C29") (pin "1") (pinfunction "1_1") (pintype "passive"))
      (node (ref "C3") (pin "1") (pinfunction "1_1") (pintype "passive"))
      (node (ref "C30") (pin "2") (pinfunction "2_2") (pintype "passive"))
      (node (ref "C4") (pin "1") (pinfunction "1_1") (pintype "passive"))
      (node (ref "C41") (pin "1") (pinfunction "1_1") (pintype "passive"))
      (node (ref "C42") (pin "1") (pinfunction "1_1") (pintype "passive"))
      (node (ref "C43") (pin "1") (pinfunction "1_1") (pintype "passive"))
      (node (ref "C44") (pin "1") (pinfunction "1_1") (pintype "passive"))
      (node (ref "C45") (pin "1") (pinfunction "1_1") (pintype "passive"))
      (node (ref "C46") (pin "1") (pinfunction "1_1") (pintype "passive"))
      (node (ref "C47") (pin "1") (pinfunction "1_1") (pintype "passive"))
      (node (ref "C48") (pin "1") (pinfunction "1_1") (pintype "passive"))
      (node (ref "C49") (pin "1") (pinfunction "1_1") (pintype "passive"))
      (node (ref "C5") (pin "1") (pinfunction "1_1") (pintype "passive"))
      (node (ref "C50") (pin "2") (pinfunction "2_2") (pintype "passive"))
      (node (ref "C6") (pin "1") (pinfunction "1_1") (pintype "passive"))
      (node (ref "C61") (pin "1") (pinfunction "1_1") (pintype "passive"))
      (node (ref "C62") (pin "1") (pinfunction "1_1") (pintype "passive"))
      (node (ref "C63") (pin "1") (pinfunction "1_1") (pintype "passive"))
      (node (ref "C64") (pin "1") (pinfunction "1_1") (pintype "passive"))
      (node (ref "C65") (pin "1") (pinfunction "1_1") (pintype "passive"))
      (node (ref "C66") (pin "1") (pinfunction "1_1") (pintype "passive"))
      (node (ref "C67") (pin "1") (pinfunction "1_1") (pintype "passive"))
      (node (ref "C68") (pin "1") (pinfunction "1_1") (pintype "passive"))
      (node (ref "C69") (pin "1") (pinfunction "1_1") (pintype "passive"))
      (node (ref "C7") (pin "1") (pinfunction "1_1") (pintype "passive"))
      (node (ref "C70") (pin "2") (pinfunction "2_2") (pintype "passive"))
      (node (ref "C8") (pin "1") (pinfunction "1_1") (pintype "passive"))
      (node (ref "J10") (pin "2") (pinfunction "2_2") (pintype "passive"))
      (node (ref "J14") (pin "2") (pinfunction "2_2") (pintype "passive"))
      (node (ref "J2") (pin "2") (pinfunction "2_2") (pintype "passive"))
      (node (ref "J6") (pin "2") (pinfunction "2_2") (pintype "passive"))
      (node (ref "LS2") (pin "N") (pinfunction "N_N") (pintype "passive"))
      (node (ref "LS3") (pin "N") (pinfunction "N_N") (pintype "passive"))
      (node (ref "LS5") (pin "N") (pinfunction "N_N") (pintype "passive"))
      (node (ref "LS7") (pin "N") (pinfunction "N_N") (pintype "passive"))
      (node (ref "R10") (pin "2") (pinfunction "2_2") (pintype "passive"))
      (node (ref "R25") (pin "1") (pinfunction "1_1") (pintype "passive"))
      (node (ref "R27") (pin "1") (pinfunction "1_1") (pintype "passive"))
      (node (ref "R34") (pin "2") (pinfunction "2_2") (pintype "passive"))
      (node (ref "R49") (pin "1") (pinfunction "1_1") (pintype "passive"))
      (node (ref "R5") (pin "1") (pinfunction "1_1") (pintype "passive"))
      (node (ref "R51") (pin "1") (pinfunction "1_1") (pintype "passive"))
      (node (ref "R58") (pin "2") (pinfunction "2_2") (pintype "passive"))
      (node (ref "R7") (pin "1") (pinfunction "1_1") (pintype "passive"))
      (node (ref "R73") (pin "1") (pinfunction "1_1") (pintype "passive"))
      (node (ref "R75") (pin "1") (pinfunction "1_1") (pintype "passive"))
      (node (ref "R82") (pin "2") (pinfunction "2_2") (pintype "passive"))
      (node (ref "U$11") (pin "P$2") (pinfunction "P$1_P$2") (pintype "bidirectional"))
      (node (ref "U$11") (pin "P$3") (pinfunction "P$1_P$3") (pintype "bidirectional"))
      (node (ref "U$11") (pin "P$4") (pinfunction "P$1_P$4") (pintype "bidirectional"))
      (node (ref "U$13") (pin "GND") (pinfunction "GND_GND") (pintype "bidirectional"))
      (node (ref "U$13") (pin "P$7") (pinfunction "GND_P$7") (pintype "bidirectional"))
      (node (ref "U$14") (pin "4") (pinfunction "OUT_4") (pintype "bidirectional"))
      (node (ref "U$15") (pin "P$11") (pinfunction "P$11_P$11") (pintype "bidirectional"))
      (node (ref "U$2") (pin "P$2") (pinfunction "P$1_P$2") (pintype "bidirectional"))
      (node (ref "U$2") (pin "P$3") (pinfunction "P$1_P$3") (pintype "bidirectional"))
      (node (ref "U$2") (pin "P$4") (pinfunction "P$1_P$4") (pintype "bidirectional"))
      (node (ref "U$21") (pin "P$2") (pinfunction "P$1_P$2") (pintype "bidirectional"))
      (node (ref "U$21") (pin "P$3") (pinfunction "P$1_P$3") (pintype "bidirectional"))
      (node (ref "U$21") (pin "P$4") (pinfunction "P$1_P$4") (pintype "bidirectional"))
      (node (ref "U$23") (pin "GND") (pinfunction "GND_GND") (pintype "bidirectional"))
      (node (ref "U$23") (pin "P$7") (pinfunction "GND_P$7") (pintype "bidirectional"))
      (node (ref "U$24") (pin "4") (pinfunction "OUT_4") (pintype "bidirectional"))
      (node (ref "U$25") (pin "P$11") (pinfunction "P$11_P$11") (pintype "bidirectional"))
      (node (ref "U$3") (pin "GND") (pinfunction "GND_GND") (pintype "bidirectional"))
      (node (ref "U$3") (pin "P$7") (pinfunction "GND_P$7") (pintype "bidirectional"))
      (node (ref "U$31") (pin "P$2") (pinfunction "P$1_P$2") (pintype "bidirectional"))
      (node (ref "U$31") (pin "P$3") (pinfunction "P$1_P$3") (pintype "bidirectional"))
      (node (ref "U$31") (pin "P$4") (pinfunction "P$1_P$4") (pintype "bidirectional"))
      (node (ref "U$33") (pin "GND") (pinfunction "GND_GND") (pintype "bidirectional"))
      (node (ref "U$33") (pin "P$7") (pinfunction "GND_P$7") (pintype "bidirectional"))
      (node (ref "U$34") (pin "4") (pinfunction "OUT_4") (pintype "bidirectional"))
      (node (ref "U$35") (pin "P$11") (pinfunction "P$11_P$11") (pintype "bidirectional"))
      (node (ref "U$4") (pin "4") (pinfunction "OUT_4") (pintype "bidirectional"))
      (node (ref "U$5") (pin "P$11") (pinfunction "P$11_P$11") (pintype "bidirectional"))
      (node (ref "U1") (pin "18") (pinfunction "GND_18") (pintype "power_in"))
      (node (ref "U1") (pin "35") (pinfunction "GND_35") (pintype "power_in"))
      (node (ref "U1") (pin "42") (pinfunction "GND_42") (pintype "power_in"))
      (node (ref "U1") (pin "49") (pinfunction "EXP_49") (pintype "power_in"))
      (node (ref "U1") (pin "5") (pinfunction "GNDANA_5") (pintype "power_in"))
      (node (ref "U10") (pin "3") (pinfunction "GND_3") (pintype "power_in"))
      (node (ref "U13") (pin "18") (pinfunction "GND_18") (pintype "power_in"))
      (node (ref "U13") (pin "35") (pinfunction "GND_35") (pintype "power_in"))
      (node (ref "U13") (pin "42") (pinfunction "GND_42") (pintype "power_in"))
      (node (ref "U13") (pin "49") (pinfunction "EXP_49") (pintype "power_in"))
      (node (ref "U13") (pin "5") (pinfunction "GNDANA_5") (pintype "power_in"))
      (node (ref "U14") (pin "3") (pinfunction "GND_3") (pintype "power_in"))
      (node (ref "U3") (pin "3") (pinfunction "GND_3") (pintype "power_in"))
      (node (ref "U5") (pin "18") (pinfunction "GND_18") (pintype "power_in"))
      (node (ref "U5") (pin "35") (pinfunction "GND_35") (pintype "power_in"))
      (node (ref "U5") (pin "42") (pinfunction "GND_42") (pintype "power_in"))
      (node (ref "U5") (pin "49") (pinfunction "EXP_49") (pintype "power_in"))
      (node (ref "U5") (pin "5") (pinfunction "GNDANA_5") (pintype "power_in"))
      (node (ref "U6") (pin "3") (pinfunction "GND_3") (pintype "power_in"))
      (node (ref "U9") (pin "18") (pinfunction "GND_18") (pintype "power_in"))
      (node (ref "U9") (pin "35") (pinfunction "GND_35") (pintype "power_in"))
      (node (ref "U9") (pin "42") (pinfunction "GND_42") (pintype "power_in"))
      (node (ref "U9") (pin "49") (pinfunction "EXP_49") (pintype "power_in"))
      (node (ref "U9") (pin "5") (pinfunction "GNDANA_5") (pintype "power_in"))
    )
    (net (code "20") (name "Net-(J1-Pad1)") (class "Default")
      (node (ref "J1") (pin "1") (pinfunction "1_1") (pintype "passive"))
      (node (ref "R6") (pin "2") (pinfunction "2_2") (pintype "passive"))
      (node (ref "U$2") (pin "P$5") (pinfunction "P$3_P$5") (pintype "bidirectional"))
      (node (ref "U$2") (pin "P$6") (pinfunction "P$3_P$6") (pintype "bidirectional"))
      (node (ref "U$2") (pin "P$7") (pinfunction "P$3_P$7") (pintype "bidirectional"))
      (node (ref "U$2") (pin "P$8") (pinfunction "P$3_P$8") (pintype "bidirectional"))
      (node (ref "U$2") (pin "P$9") (pinfunction "P$3_P$9") (pintype "bidirectional"))
    )
    (net (code "21") (name "Net-(J5-Pad1)") (class "Default")
      (node (ref "J5") (pin "1") (pinfunction "1_1") (pintype "passive"))
      (node (ref "R26") (pin "2") (pinfunction "2_2") (pintype "passive"))
      (node (ref "U$11") (pin "P$5") (pinfunction "P$3_P$5") (pintype "bidirectional"))
      (node (ref "U$11") (pin "P$6") (pinfunction "P$3_P$6") (pintype "bidirectional"))
      (node (ref "U$11") (pin "P$7") (pinfunction "P$3_P$7") (pintype "bidirectional"))
      (node (ref "U$11") (pin "P$8") (pinfunction "P$3_P$8") (pintype "bidirectional"))
      (node (ref "U$11") (pin "P$9") (pinfunction "P$3_P$9") (pintype "bidirectional"))
    )
    (net (code "22") (name "Net-(J9-Pad1)") (class "Default")
      (node (ref "J9") (pin "1") (pinfunction "1_1") (pintype "passive"))
      (node (ref "R50") (pin "2") (pinfunction "2_2") (pintype "passive"))
      (node (ref "U$21") (pin "P$5") (pinfunction "P$3_P$5") (pintype "bidirectional"))
      (node (ref "U$21") (pin "P$6") (pinfunction "P$3_P$6") (pintype "bidirectional"))
      (node (ref "U$21") (pin "P$7") (pinfunction "P$3_P$7") (pintype "bidirectional"))
      (node (ref "U$21") (pin "P$8") (pinfunction "P$3_P$8") (pintype "bidirectional"))
      (node (ref "U$21") (pin "P$9") (pinfunction "P$3_P$9") (pintype "bidirectional"))
    )
    (net (code "23") (name "Net-(J13-Pad1)") (class "Default")
      (node (ref "J13") (pin "1") (pinfunction "1_1") (pintype "passive"))
      (node (ref "R74") (pin "2") (pinfunction "2_2") (pintype "passive"))
      (node (ref "U$31") (pin "P$5") (pinfunction "P$3_P$5") (pintype "bidirectional"))
      (node (ref "U$31") (pin "P$6") (pinfunction "P$3_P$6") (pintype "bidirectional"))
      (node (ref "U$31") (pin "P$7") (pinfunction "P$3_P$7") (pintype "bidirectional"))
      (node (ref "U$31") (pin "P$8") (pinfunction "P$3_P$8") (pintype "bidirectional"))
      (node (ref "U$31") (pin "P$9") (pinfunction "P$3_P$9") (pintype "bidirectional"))
    )
    (net (code "24") (name "Net-(R6-Pad1)") (class "Default")
      (node (ref "R6") (pin "1") (pinfunction "1_1") (pintype "passive"))
      (node (ref "R7") (pin "2") (pinfunction "2_2") (pintype "passive"))
      (node (ref "R9") (pin "1") (pinfunction "1_1") (pintype "passive"))
    )
    (net (code "25") (name "Net-(R10-Pad1)") (class "Default")
      (node (ref "R10") (pin "1") (pinfunction "1_1") (pintype "passive"))
      (node (ref "R11") (pin "1") (pinfunction "1_1") (pintype "passive"))
      (node (ref "R12") (pin "1") (pinfunction "1_1") (pintype "passive"))
    )
    (net (code "26") (name "Net-(R26-Pad1)") (class "Default")
      (node (ref "R26") (pin "1") (pinfunction "1_1") (pintype "passive"))
      (node (ref "R27") (pin "2") (pinfunction "2_2") (pintype "passive"))
      (node (ref "R29") (pin "1") (pinfunction "1_1") (pintype "passive"))
    )
    (net (code "27") (name "Net-(R34-Pad1)") (class "Default")
      (node (ref "R34") (pin "1") (pinfunction "1_1") (pintype "passive"))
      (node (ref "R35") (pin "1") (pinfunction "1_1") (pintype "passive"))
      (node (ref "R36") (pin "1") (pinfunction "1_1") (pintype "passive"))
    )
    (net (code "28") (name "Net-(R50-Pad1)") (class "Default")
      (node (ref "R50") (pin "1") (pinfunction "1_1") (pintype "passive"))
      (node (ref "R51") (pin "2") (pinfunction "2_2") (pintype "passive"))
      (node (ref "R53") (pin "1") (pinfunction "1_1") (pintype "passive"))
    )
    (net (code "29") (name "Net-(R58-Pad1)") (class "Default")
      (node (ref "R58") (pin "1") (pinfunction "1_1") (pintype "passive"))
      (node (ref "R59") (pin "1") (pinfunction "1_1") (pintype "passive"))
      (node (ref "R60") (pin "1") (pinfunction "1_1") (pintype "passive"))
    )
    (net (code "30") (name "Net-(R74-Pad1)") (class "Default")
      (node (ref "R74") (pin "1") (pinfunction "1_1") (pintype "passive"))
      (node (ref "R75") (pin "2") (pinfunction "2_2") (pintype "passive"))
      (node (ref "R77") (pin "1") (pinfunction "1_1") (pintype "passive"))
    )
    (net (code "31") (name "Net-(R82-Pad1)") (class "Default")
      (node (ref "R82") (pin "1") (pinfunction "1_1") (pintype "passive"))
      (node (ref "R83") (pin "1") (pinfunction "1_1") (pintype "passive"))
      (node (ref "R84") (pin "1") (pinfunction "1_1") (pintype "passive"))
    )
    (net (code "32") (name "Net-(U$2-P$2)") (class "Default")
      (node (ref "R5") (pin "2") (pinfunction "2_2") (pintype "passive"))
      (node (ref "R8") (pin "2") (pinfunction "2_2") (pintype "passive"))
      (node (ref "U$2") (pin "P$1") (pinfunction "P$2_P$1") (pintype "bidirectional"))
    )
    (net (code "33") (name "Net-(U$11-P$2)") (class "Default")
      (node (ref "R25") (pin "2") (pinfunction "2_2") (pintype "passive"))
      (node (ref "R28") (pin "2") (pinfunction "2_2") (pintype "passive"))
      (node (ref "U$11") (pin "P$1") (pinfunction "P$2_P$1") (pintype "bidirectional"))
    )
    (net (code "34") (name "Net-(U$21-P$2)") (class "Default")
      (node (ref "R49") (pin "2") (pinfunction "2_2") (pintype "passive"))
      (node (ref "R52") (pin "2") (pinfunction "2_2") (pintype "passive"))
      (node (ref "U$21") (pin "P$1") (pinfunction "P$2_P$1") (pintype "bidirectional"))
    )
    (net (code "35") (name "Net-(U$31-P$2)") (class "Default")
      (node (ref "R73") (pin "2") (pinfunction "2_2") (pintype "passive"))
      (node (ref "R76") (pin "2") (pinfunction "2_2") (pintype "passive"))
      (node (ref "U$31") (pin "P$1") (pinfunction "P$2_P$1") (pintype "bidirectional"))
    )
    (net (code "36") (name "Net-(U1-PA00)") (class "Default")
      (node (ref "C7") (pin "2") (pinfunction "2_2") (pintype "passive"))
      (node (ref "U$1") (pin "P$2") (pinfunction "P$2_P$2") (pintype "bidirectional"))
      (node (ref "U1") (pin "1") (pinfunction "PA00_1") (pintype "bidirectional"))
    )
    (net (code "37") (name "Net-(U1-PA01)") (class "Default")
      (node (ref "C6") (pin "2") (pinfunction "2_2") (pintype "passive"))
      (node (ref "U$1") (pin "P$1") (pinfunction "P$1_P$1") (pintype "bidirectional"))
      (node (ref "U1") (pin "2") (pinfunction "PA01_2") (pintype "bidirectional"))
    )
    (net (code "38") (name "Net-(U1-VDDANA)") (class "Default")
      (node (ref "C3") (pin "2") (pinfunction "2_2") (pintype "passive"))
      (node (ref "R1") (pin "1") (pinfunction "1_1") (pintype "passive"))
      (node (ref "U1") (pin "6") (pinfunction "VDDANA_6") (pintype "power_in"))
    )
    (net (code "39") (name "Net-(U1-VDDCORE)") (class "Default")
      (node (ref "C5") (pin "2") (pinfunction "2_2") (pintype "passive"))
      (node (ref "U1") (pin "43") (pinfunction "VDDCORE_43") (pintype "power_in"))
    )
    (net (code "40") (name "Net-(U5-PA00)") (class "Default")
      (node (ref "C27") (pin "2") (pinfunction "2_2") (pintype "passive"))
      (node (ref "U$12") (pin "P$2") (pinfunction "P$2_P$2") (pintype "bidirectional"))
      (node (ref "U5") (pin "1") (pinfunction "PA00_1") (pintype "bidirectional"))
    )
    (net (code "41") (name "Net-(U5-PA01)") (class "Default")
      (node (ref "C26") (pin "2") (pinfunction "2_2") (pintype "passive"))
      (node (ref "U$12") (pin "P$1") (pinfunction "P$1_P$1") (pintype "bidirectional"))
      (node (ref "U5") (pin "2") (pinfunction "PA01_2") (pintype "bidirectional"))
    )
    (net (code "42") (name "Net-(U5-VDDANA)") (class "Default")
      (node (ref "C23") (pin "2") (pinfunction "2_2") (pintype "passive"))
      (node (ref "R30") (pin "1") (pinfunction "1_1") (pintype "passive"))
      (node (ref "U5") (pin "6") (pinfunction "VDDANA_6") (pintype "power_in"))
    )
    (net (code "43") (name "Net-(U5-VDDCORE)") (class "Default")
      (node (ref "C25") (pin "2") (pinfunction "2_2") (pintype "passive"))
      (node (ref "U5") (pin "43") (pinfunction "VDDCORE_43") (pintype "power_in"))
    )
    (net (code "44") (name "Net-(U9-PA00)") (class "Default")
      (node (ref "C47") (pin "2") (pinfunction "2_2") (pintype "passive"))
      (node (ref "U$22") (pin "P$2") (pinfunction "P$2_P$2") (pintype "bidirectional"))
      (node (ref "U9") (pin "1") (pinfunction "PA00_1") (pintype "bidirectional"))
    )
    (net (code "45") (name "Net-(U9-PA01)") (class "Default")
      (node (ref "C46") (pin "2") (pinfunction "2_2") (pintype "passive"))
      (node (ref "U$22") (pin "P$1") (pinfunction "P$1_P$1") (pintype "bidirectional"))
      (node (ref "U9") (pin "2") (pinfunction "PA01_2") (pintype "bidirectional"))
    )
    (net (code "46") (name "Net-(U9-VDDANA)") (class "Default")
      (node (ref "C43") (pin "2") (pinfunction "2_2") (pintype "passive"))
      (node (ref "R54") (pin "1") (pinfunction "1_1") (pintype "passive"))
      (node (ref "U9") (pin "6") (pinfunction "VDDANA_6") (pintype "power_in"))
    )
    (net (code "47") (name "Net-(U9-VDDCORE)") (class "Default")
      (node (ref "C45") (pin "2") (pinfunction "2_2") (pintype "passive"))
      (node (ref "U9") (pin "43") (pinfunction "VDDCORE_43") (pintype "power_in"))
    )
    (net (code "48") (name "Net-(U13-PA00)") (class "Default")
      (node (ref "C67") (pin "2") (pinfunction "2_2") (pintype "passive"))
      (node (ref "U$32") (pin "P$2") (pinfunction "P$2_P$2") (pintype "bidirectional"))
      (node (ref "U13") (pin "1") (pinfunction "PA00_1") (pintype "bidirectional"))
    )
    (net (code "49") (name "Net-(U13-PA01)") (class "Default")
      (node (ref "C66") (pin "2") (pinfunction "2_2") (pintype "passive"))
      (node (ref "U$32") (pin "P$1") (pinfunction "P$1_P$1") (pintype "bidirectional"))
      (node (ref "U13") (pin "2") (pinfunction "PA01_2") (pintype "bidirectional"))
    )
    (net (code "50") (name "Net-(U13-VDDANA)") (class "Default")
      (node (ref "C63") (pin "2") (pinfunction "2_2") (pintype "passive"))
      (node (ref "R78") (pin "1") (pinfunction "1_1") (pintype "passive"))
      (node (ref "U13") (pin "6") (pinfunction "VDDANA_6") (pintype "power_in"))
    )
    (net (code "51") (name "Net-(U13-VDDCORE)") (class "Default")
      (node (ref "C65") (pin "2") (pinfunction "2_2") (pintype "passive"))
      (node (ref "U13") (pin "43") (pinfunction "VDDCORE_43") (pintype "power_in"))
    )
    (net (code "52") (name "unconnected-(U$3-PadADJ)") (class "Default")
      (node (ref "U$3") (pin "ADJ") (pinfunction "ADJ_ADJ") (pintype "bidirectional"))
    )
    (net (code "53") (name "unconnected-(U$3-PadNC)") (class "Default")
      (node (ref "U$3") (pin "NC") (pinfunction "NC_NC") (pintype "bidirectional"))
    )
    (net (code "54") (name "unconnected-(U$4-IN-Pad1)") (class "Default")
      (node (ref "U$4") (pin "1") (pinfunction "IN_1") (pintype "bidirectional"))
    )
    (net (code "55") (name "unconnected-(U$5-PadP$1)") (class "Default")
      (node (ref "U$5") (pin "P$1") (pinfunction "P$1_P$1") (pintype "bidirectional"))
    )
    (net (code "56") (name "unconnected-(U$5-PadP$2)") (class "Default")
      (node (ref "U$5") (pin "P$2") (pinfunction "P$2_P$2") (pintype "bidirectional"))
    )
    (net (code "57") (name "unconnected-(U$5-PadP$3)") (class "Default")
      (node (ref "U$5") (pin "P$3") (pinfunction "P$3_P$3") (pintype "bidirectional"))
    )
    (net (code "58") (name "unconnected-(U$5-PadP$4)") (class "Default")
      (node (ref "U$5") (pin "P$4") (pinfunction "P$4_P$4") (pintype "bidirectional"))
    )
    (net (code "59") (name "unconnected-(U$5-PadP$5)") (class "Default")
      (node (ref "U$5") (pin "P$5") (pinfunction "P$5_P$5") (pintype "bidirectional"))
    )
    (net (code "60") (name "unconnected-(U$13-PadADJ)") (class "Default")
      (node (ref "U$13") (pin "ADJ") (pinfunction "ADJ_ADJ") (pintype "bidirectional"))
    )
    (net (code "61") (name "unconnected-(U$13-PadNC)") (class "Default")
      (node (ref "U$13") (pin "NC") (pinfunction "NC_NC") (pintype "bidirectional"))
    )
    (net (code "62") (name "unconnected-(U$14-IN-Pad1)") (class "Default")
      (node (ref "U$14") (pin "1") (pinfunction "IN_1") (pintype "bidirectional"))
    )
    (net (code "63") (name "unconnected-(U$15-PadP$1)") (class "Default")
      (node (ref "U$15") (pin "P$1") (pinfunction "P$1_P$1") (pintype "bidirectional"))
    )
    (net (code "64") (name "unconnected-(U$15-PadP$2)") (class "Default")
      (node (ref "U$15") (pin "P$2") (pinfunction "P$2_P$2") (pintype "bidirectional"))
    )
    (net (code "65") (name "unconnected-(U$15-PadP$3)") (class "Default")
      (node (ref "U$15") (pin "P$3") (pinfunction "P$3_P$3") (pintype "bidirectional"))
    )
    (net (code "66") (name "unconnected-(U$15-PadP$4)") (class "Default")
      (node (ref "U$15") (pin "P$4") (pinfunction "P$4_P$4") (pintype "bidirectional"))
    )
    (net (code "67") (name "unconnected-(U$15-PadP$5)") (class "Default")
      (node (ref "U$15") (pin "P$5") (pinfunction "P$5_P$5") (pintype "bidirectional"))
    )
    (net (code "68") (name "unconnected-(U$23-PadADJ)") (class "Default")
      (node (ref "U$23") (pin "ADJ") (pinfunction "ADJ_ADJ") (pintype "bidirectional"))
    )
    (net (code "69") (name "unconnected-(U$23-PadNC)") (class "Default")
      (node (ref "U$23") (pin "NC") (pinfunction "NC_NC") (pintype "bidirectional"))
    )
    (net (code "70") (name "unconnected-(U$24-IN-Pad1)") (class "Default")
      (node (ref "U$24") (pin "1") (pinfunction "IN_1") (pintype "bidirectional"))
    )
    (net (code "71") (name "unconnected-(U$25-PadP$1)") (class "Default")
      (node (ref "U$25") (pin "P$1") (pinfunction "P$1_P$1") (pintype "bidirectional"))
    )
    (net (code "72") (name "unconnected-(U$25-PadP$2)") (class "Default")
      (node (ref "U$25") (pin "P$2") (pinfunction "P$2_P$2") (pintype "bidirectional"))
    )
    (net (code "73") (name "unconnected-(U$25-PadP$3)") (class "Default")
      (node (ref "U$25") (pin "P$3") (pinfunction "P$3_P$3") (pintype "bidirectional"))
    )
    (net (code "74") (name "unconnected-(U$25-PadP$4)") (class "Default")
      (node (ref "U$25") (pin "P$4") (pinfunction "P$4_P$4") (pintype "bidirectional"))
    )
    (net (code "75") (name "unconnected-(U$25-PadP$5)") (class "Default")
      (node (ref "U$25") (pin "P$5") (pinfunction "P$5_P$5") (pintype "bidirectional"))
    )
    (net (code "76") (name "unconnected-(U$33-PadADJ)") (class "Default")
      (node (ref "U$33") (pin "ADJ") (pinfunction "ADJ_ADJ") (pintype "bidirectional"))
    )
    (net (code "77") (name "unconnected-(U$33-PadNC)") (class "Default")
      (node (ref "U$33") (pin "NC") (pinfunction "NC_NC") (pintype "bidirectional"))
    )
    (net (code "78") (name "unconnected-(U$34-IN-Pad1)") (class "Default")
      (node (ref "U$34") (pin "1") (pinfunction "IN_1") (pintype "bidirectional"))
    )
    (net (code "79") (name "unconnected-(U$35-PadP$1)") (class "Default")
      (node (ref "U$35") (pin "P$1") (pinfunction "P$1_P$1") (pintype "bidirectional"))
    )
    (net (code "80") (name "unconnected-(U$35-PadP$2)") (class "Default")
      (node (ref "U$35") (pin "P$2") (pinfunction "P$2_P$2") (pintype "bidirectional"))
    )
    (net (code "81") (name "unconnected-(U$35-PadP$3)") (class "Default")
      (node (ref "U$35") (pin "P$3") (pinfunction "P$3_P$3") (pintype "bidirectional"))
    )
    (net (code "82") (name "unconnected-(U$35-PadP$4)") (class "Default")
      (node (ref "U$35") (pin "P$4") (pinfunction "P$4_P$4") (pintype "bidirectional"))
    )
    (net (code "83") (name "unconnected-(U$35-PadP$5)") (class "Default")
      (node (ref "U$35") (pin "P$5") (pinfunction "P$5_P$5") (pintype "bidirectional"))
    )
    (net (code "84") (name "unconnected-(U1-PA02-Pad3)") (class "Default")
      (node (ref "U1") (pin "3") (pinfunction "PA02_3") (pintype "bidirectional"))
    )
    (net (code "85") (name "unconnected-(U1-PA03-Pad4)") (class "Default")
      (node (ref "U1") (pin "4") (pinfunction "PA03_4") (pintype "bidirectional"))
    )
    (net (code "86") (name "unconnected-(U1-PA06-Pad11)") (class "Default")
      (node (ref "U1") (pin "11") (pinfunction "PA06_11") (pintype "bidirectional"))
    )
    (net (code "87") (name "unconnected-(U1-PA07-Pad12)") (class "Default")
      (node (ref "U1") (pin "12") (pinfunction "PA07_12") (pintype "bidirectional"))
    )
    (net (code "88") (name "unconnected-(U1-PA09-Pad14)") (class "Default")
      (node (ref "U1") (pin "14") (pinfunction "PA09_14") (pintype "bidirectional"))
    )
    (net (code "89") (name "unconnected-(U1-PA10-Pad15)") (class "Default")
      (node (ref "U1") (pin "15") (pinfunction "PA10_15") (pintype "bidirectional"))
    )
    (net (code "90") (name "unconnected-(U1-PA11-Pad16)") (class "Default")
      (node (ref "U1") (pin "16") (pinfunction "PA11_16") (pintype "bidirectional"))
    )
    (net (code "91") (name "unconnected-(U1-PA12-Pad21)") (class "Default")
      (node (ref "U1") (pin "21") (pinfunction "PA12_21") (pintype "bidirectional"))
    )
    (net (code "92") (name "unconnected-(U1-PA13-Pad22)") (class "Default")
      (node (ref "U1") (pin "22") (pinfunction "PA13_22") (pintype "bidirectional"))
    )
    (net (code "93") (name "unconnected-(U1-PA14-Pad23)") (class "Default")
      (node (ref "U1") (pin "23") (pinfunction "PA14_23") (pintype "bidirectional"))
    )
    (net (code "94") (name "unconnected-(U1-PA20-Pad29)") (class "Default")
      (node (ref "U1") (pin "29") (pinfunction "PA20_29") (pintype "bidirectional"))
    )
    (net (code "95") (name "unconnected-(U1-PA24-Pad33)") (class "Default")
      (node (ref "U1") (pin "33") (pinfunction "PA24_33") (pintype "bidirectional"))
    )
    (net (code "96") (name "unconnected-(U1-PA25-Pad34)") (class "Default")
      (node (ref "U1") (pin "34") (pinfunction "PA25_34") (pintype "bidirectional"))
    )
    (net (code "97") (name "unconnected-(U1-PA27-Pad39)") (class "Default")
      (node (ref "U1") (pin "39") (pinfunction "PA27_39") (pintype "bidirectional"))
    )
    (net (code "98") (name "unconnected-(U1-PA28-Pad41)") (class "Default")
      (node (ref "U1") (pin "41") (pinfunction "PA28_41") (pintype "bidirectional"))
    )
    (net (code "99") (name "unconnected-(U1-PB02-Pad47)") (class "Default")
      (node (ref "U1") (pin "47") (pinfunction "PB02_47") (pintype "bidirectional"))
    )
    (net (code "100") (name "unconnected-(U1-PB03-Pad48)") (class "Default")
      (node (ref "U1") (pin "48") (pinfunction "PB03_48") (pintype "bidirectional"))
    )
    (net (code "101") (name "unconnected-(U1-PB08-Pad7)") (class "Default")
      (node (ref "U1") (pin "7") (pinfunction "PB08_7") (pintype "bidirectional"))
    )
    (net (code "102") (name "unconnected-(U1-PB09-Pad8)") (class "Default")
      (node (ref "U1") (pin "8") (pinfunction "PB09_8") (pintype "bidirectional"))
    )
    (net (code "103") (name "unconnected-(U1-PB10-Pad19)") (class "Default")
      (node (ref "U1") (pin "19") (pinfunction "PB10_19") (pintype "bidirectional"))
    )
    (net (code "104") (name "unconnected-(U1-PB11-Pad20)") (class "Default")
      (node (ref "U1") (pin "20") (pinfunction "PB11_20") (pintype "bidirectional"))
    )
    (net (code "105") (name "unconnected-(U5-PA02-Pad3)") (class "Default")
      (node (ref "U5") (pin "3") (pinfunction "PA02_3") (pintype "bidirectional"))
    )
    (net (code "106") (name "unconnected-(U5-PA03-Pad4)") (class "Default")
      (node (ref "U5") (pin "4") (pinfunction "PA03_4") (pintype "bidirectional"))
    )
    (net (code "107") (name "unconnected-(U5-PA06-Pad11)") (class "Default")
      (node (ref "U5") (pin "11") (pinfunction "PA06_11") (pintype "bidirectional"))
    )
    (net (code "108") (name "unconnected-(U5-PA07-Pad12)") (class "Default")
      (node (ref "U5") (pin "12") (pinfunction "PA07_12") (pintype "bidirectional"))
    )
    (net (code "109") (name "unconnected-(U5-PA09-Pad14)") (class "Default")
      (node (ref "U5") (pin "14") (pinfunction "PA09_14") (pintype "bidirectional"))
    )
    (net (code "110") (name "unconnected-(U5-PA10-Pad15)") (class "Default")
      (node (ref "U5") (pin "15") (pinfunction "PA10_15") (pintype "bidirectional"))
    )
    (net (code "111") (name "unconnected-(U5-PA11-Pad16)") (class "Default")
      (node (ref "U5") (pin "16") (pinfunction "PA11_16") (pintype "bidirectional"))
    )
    (net (code "112") (name "unconnected-(U5-PA12-Pad21)") (class "Default")
      (node (ref "U5") (pin "21") (pinfunction "PA12_21") (pintype "bidirectional"))
    )
    (net (code "113") (name "unconnected-(U5-PA13-Pad22)") (class "Default")
      (node (ref "U5") (pin "22") (pinfunction "PA13_22") (pintype "bidirectional"))
    )
    (net (code "114") (name "unconnected-(U5-PA14-Pad23)") (class "Default")
      (node (ref "U5") (pin "23") (pinfunction "PA14_23") (pintype "bidirectional"))
    )
    (net (code "115") (name "unconnected-(U5-PA20-Pad29)") (class "Default")
      (node (ref "U5") (pin "29") (pinfunction "PA20_29") (pintype "bidirectional"))
    )
    (net (code "116") (name "unconnected-(U5-PA24-Pad33)") (class "Default")
      (node (ref "U5") (pin "33") (pinfunction "PA24_33") (pintype "bidirectional"))
    )
    (net (code "117") (name "unconnected-(U5-PA25-Pad34)") (class "Default")
      (node (ref "U5") (pin "34") (pinfunction "PA25_34") (pintype "bidirectional"))
    )
    (net (code "118") (name "unconnected-(U5-PA27-Pad39)") (class "Default")
      (node (ref "U5") (pin "39") (pinfunction "PA27_39") (pintype "bidirectional"))
    )
    (net (code "119") (name "unconnected-(U5-PA28-Pad41)") (class "Default")
      (node (ref "U5") (pin "41") (pinfunction "PA28_41") (pintype "bidirectional"))
    )
    (net (code "120") (name "unconnected-(U5-PB02-Pad47)") (class "Default")
      (node (ref "U5") (pin "47") (pinfunction "PB02_47") (pintype "bidirectional"))
    )
    (net (code "121") (name "unconnected-(U5-PB03-Pad48)") (class "Default")
      (node (ref "U5") (pin "48") (pinfunction "PB03_48") (pintype "bidirectional"))
    )
    (net (code "122") (name "unconnected-(U5-PB08-Pad7)") (class "Default")
      (node (ref "U5") (pin "7") (pinfunction "PB08_7") (pintype "bidirectional"))
    )
    (net (code "123") (name "unconnected-(U5-PB09-Pad8)") (class "Default")
      (node (ref "U5") (pin "8") (pinfunction "PB09_8") (pintype "bidirectional"))
    )
    (net (code "124") (name "unconnected-(U5-PB10-Pad19)") (class "Default")
      (node (ref "U5") (pin "19") (pinfunction "PB10_19") (pintype "bidirectional"))
    )
    (net (code "125") (name "unconnected-(U5-PB11-Pad20)") (class "Default")
      (node (ref "U5") (pin "20") (pinfunction "PB11_20") (pintype "bidirectional"))
    )
    (net (code "126") (name "unconnected-(U9-PA02-Pad3)") (class "Default")
      (node (ref "U9") (pin "3") (pinfunction "PA02_3") (pintype "bidirectional"))
    )
    (net (code "127") (name "unconnected-(U9-PA03-Pad4)") (class "Default")
      (node (ref "U9") (pin "4") (pinfunction "PA03_4") (pintype "bidirectional"))
    )
    (net (code "128") (name "unconnected-(U9-PA06-Pad11)") (class "Default")
      (node (ref "U9") (pin "11") (pinfunction "PA06_11") (pintype "bidirectional"))
    )
    (net (code "129") (name "unconnected-(U9-PA07-Pad12)") (class "Default")
      (node (ref "U9") (pin "12") (pinfunction "PA07_12") (pintype "bidirectional"))
    )
    (net (code "130") (name "unconnected-(U9-PA09-Pad14)") (class "Default")
      (node (ref "U9") (pin "14") (pinfunction "PA09_14") (pintype "bidirectional"))
    )
    (net (code "131") (name "unconnected-(U9-PA10-Pad15)") (class "Default")
      (node (ref "U9") (pin "15") (pinfunction "PA10_15") (pintype "bidirectional"))
    )
    (net (code "132") (name "unconnected-(U9-PA11-Pad16)") (class "Default")
      (node (ref "U9") (pin "16") (pinfunction "PA11_16") (pintype "bidirectional"))
    )
    (net (code "133") (name "unconnected-(U9-PA12-Pad21)") (class "Default")
      (node (ref "U9") (pin "21") (pinfunction "PA12_21") (pintype "bidirectional"))
    )
    (net (code "134") (name "unconnected-(U9-PA13-Pad22)") (class "Default")
      (node (ref "U9") (pin "22") (pinfunction "PA13_22") (pintype "bidirectional"))
    )
    (net (code "135") (name "unconnected-(U9-PA14-Pad23)") (class "Default")
      (node (ref "U9") (pin "23") (pinfunction "PA14_23") (pintype "bidirectional"))
    )
    (net (code "136") (name "unconnected-(U9-PA20-Pad29)") (class "Default")
      (node (ref "U9") (pin "29") (pinfunction "PA20_29") (pintype "bidirectional"))
    )
    (net (code "137") (name "unconnected-(U9-PA24-Pad33)") (class "Default")
      (node (ref "U9") (pin "33") (pinfunction "PA24_33") (pintype "bidirectional"))
    )
    (net (code "138") (name "unconnected-(U9-PA25-Pad34)") (class "Default")
      (node (ref "U9") (pin "34") (pinfunction "PA25_34") (pintype "bidirectional"))
    )
    (net (code "139") (name "unconnected-(U9-PA27-Pad39)") (class "Default")
      (node (ref "U9") (pin "39") (pinfunction "PA27_39") (pintype "bidirectional"))
    )
    (net (code "140") (name "unconnected-(U9-PA28-Pad41)") (class "Default")
      (node (ref "U9") (pin "41") (pinfunction "PA28_41") (pintype "bidirectional"))
    )
    (net (code "141") (name "unconnected-(U9-PB02-Pad47)") (class "Default")
      (node (ref "U9") (pin "47") (pinfunction "PB02_47") (pintype "bidirectional"))
    )
    (net (code "142") (name "unconnected-(U9-PB03-Pad48)") (class "Default")
      (node (ref "U9") (pin "48") (pinfunction "PB03_48") (pintype "bidirectional"))
    )
    (net (code "143") (name "unconnected-(U9-PB08-Pad7)") (class "Default")
      (node (ref "U9") (pin "7") (pinfunction "PB08_7") (pintype "bidirectional"))
    )
    (net (code "144") (name "unconnected-(U9-PB09-Pad8)") (class "Default")
      (node (ref "U9") (pin "8") (pinfunction "PB09_8") (pintype "bidirectional"))
    )
    (net (code "145") (name "unconnected-(U9-PB10-Pad19)") (class "Default")
      (node (ref "U9") (pin "19") (pinfunction "PB10_19") (pintype "bidirectional"))
    )
    (net (code "146") (name "unconnected-(U9-PB11-Pad20)") (class "Default")
      (node (ref "U9") (pin "20") (pinfunction "PB11_20") (pintype "bidirectional"))
    )
    (net (code "147") (name "unconnected-(U13-PA02-Pad3)") (class "Default")
      (node (ref "U13") (pin "3") (pinfunction "PA02_3") (pintype "bidirectional"))
    )
    (net (code "148") (name "unconnected-(U13-PA03-Pad4)") (class "Default")
      (node (ref "U13") (pin "4") (pinfunction "PA03_4") (pintype "bidirectional"))
    )
    (net (code "149") (name "unconnected-(U13-PA06-Pad11)") (class "Default")
      (node (ref "U13") (pin "11") (pinfunction "PA06_11") (pintype "bidirectional"))
    )
    (net (code "150") (name "unconnected-(U13-PA07-Pad12)") (class "Default")
      (node (ref "U13") (pin "12") (pinfunction "PA07_12") (pintype "bidirectional"))
    )
    (net (code "151") (name "unconnected-(U13-PA09-Pad14)") (class "Default")
      (node (ref "U13") (pin "14") (pinfunction "PA09_14") (pintype "bidirectional"))
    )
    (net (code "152") (name "unconnected-(U13-PA10-Pad15)") (class "Default")
      (node (ref "U13") (pin "15") (pinfunction "PA10_15") (pintype "bidirectional"))
    )
    (net (code "153") (name "unconnected-(U13-PA11-Pad16)") (class "Default")
      (node (ref "U13") (pin "16") (pinfunction "PA11_16") (pintype "bidirectional"))
    )
    (net (code "154") (name "unconnected-(U13-PA12-Pad21)") (class "Default")
      (node (ref "U13") (pin "21") (pinfunction "PA12_21") (pintype "bidirectional"))
    )
    (net (code "155") (name "unconnected-(U13-PA13-Pad22)") (class "Default")
      (node (ref "U13") (pin "22") (pinfunction "PA13_22") (pintype "bidirectional"))
    )
    (net (code "156") (name "unconnected-(U13-PA14-Pad23)") (class "Default")
      (node (ref "U13") (pin "23") (pinfunction "PA14_23") (pintype "bidirectional"))
    )
    (net (code "157") (name "unconnected-(U13-PA20-Pad29)") (class "Default")
      (node (ref "U13") (pin "29") (pinfunction "PA20_29") (pintype "bidirectional"))
    )
    (net (code "158") (name "unconnected-(U13-PA24-Pad33)") (class "Default")
      (node (ref "U13") (pin "33") (pinfunction "PA24_33") (pintype "bidirectional"))
    )
    (net (code "159") (name "unconnected-(U13-PA25-Pad34)") (class "Default")
      (node (ref "U13") (pin "34") (pinfunction "PA25_34") (pintype "bidirectional"))
    )
    (net (code "160") (name "unconnected-(U13-PA27-Pad39)") (class "Default")
      (node (ref "U13") (pin "39") (pinfunction "PA27_39") (pintype "bidirectional"))
    )
    (net (code "161") (name "unconnected-(U13-PA28-Pad41)") (class "Default")
      (node (ref "U13") (pin "41") (pinfunction "PA28_41") (pintype "bidirectional"))
    )
    (net (code "162") (name "unconnected-(U13-PB02-Pad47)") (class "Default")
      (node (ref "U13") (pin "47") (pinfunction "PB02_47") (pintype "bidirectional"))
    )
    (net (code "163") (name "unconnected-(U13-PB03-Pad48)") (class "Default")
      (node (ref "U13") (pin "48") (pinfunction "PB03_48") (pintype "bidirectional"))
    )
    (net (code "164") (name "unconnected-(U13-PB08-Pad7)") (class "Default")
      (node (ref "U13") (pin "7") (pinfunction "PB08_7") (pintype "bidirectional"))
    )
    (net (code "165") (name "unconnected-(U13-PB09-Pad8)") (class "Default")
      (node (ref "U13") (pin "8") (pinfunction "PB09_8") (pintype "bidirectional"))
    )
    (net (code "166") (name "unconnected-(U13-PB10-Pad19)") (class "Default")
      (node (ref "U13") (pin "19") (pinfunction "PB10_19") (pintype "bidirectional"))
    )
    (net (code "167") (name "unconnected-(U13-PB11-Pad20)") (class "Default")
      (node (ref "U13") (pin "20") (pinfunction "PB11_20") (pintype "bidirectional"))
    )
  )
)
